# AnalogConversion_v1.net
KiCad netlist of a schematic drawn in EAGLE
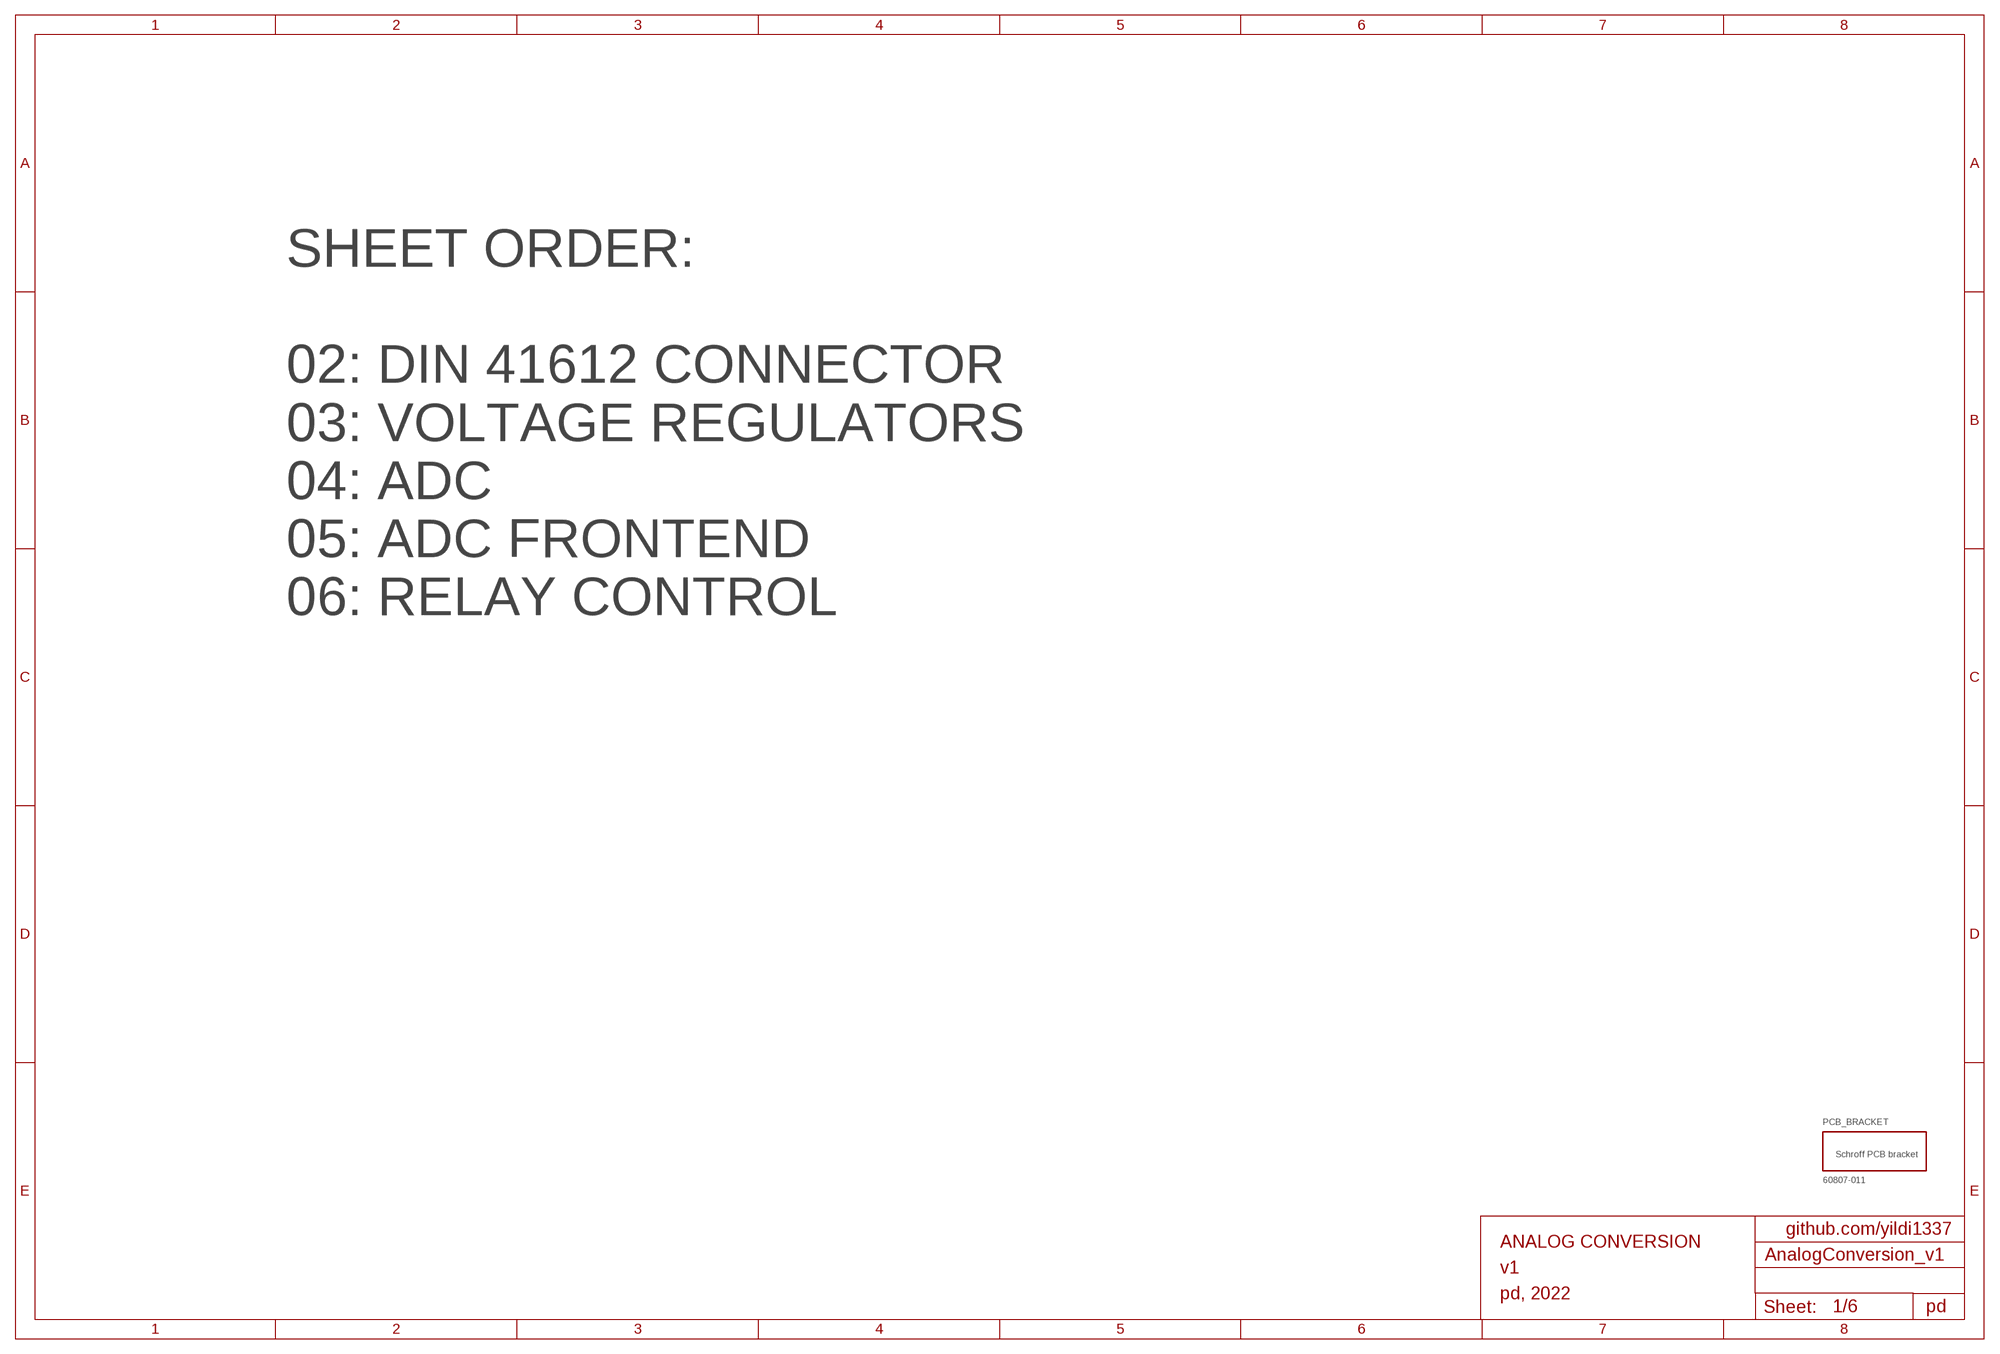
[diagram p0: schematic, sheet 1]
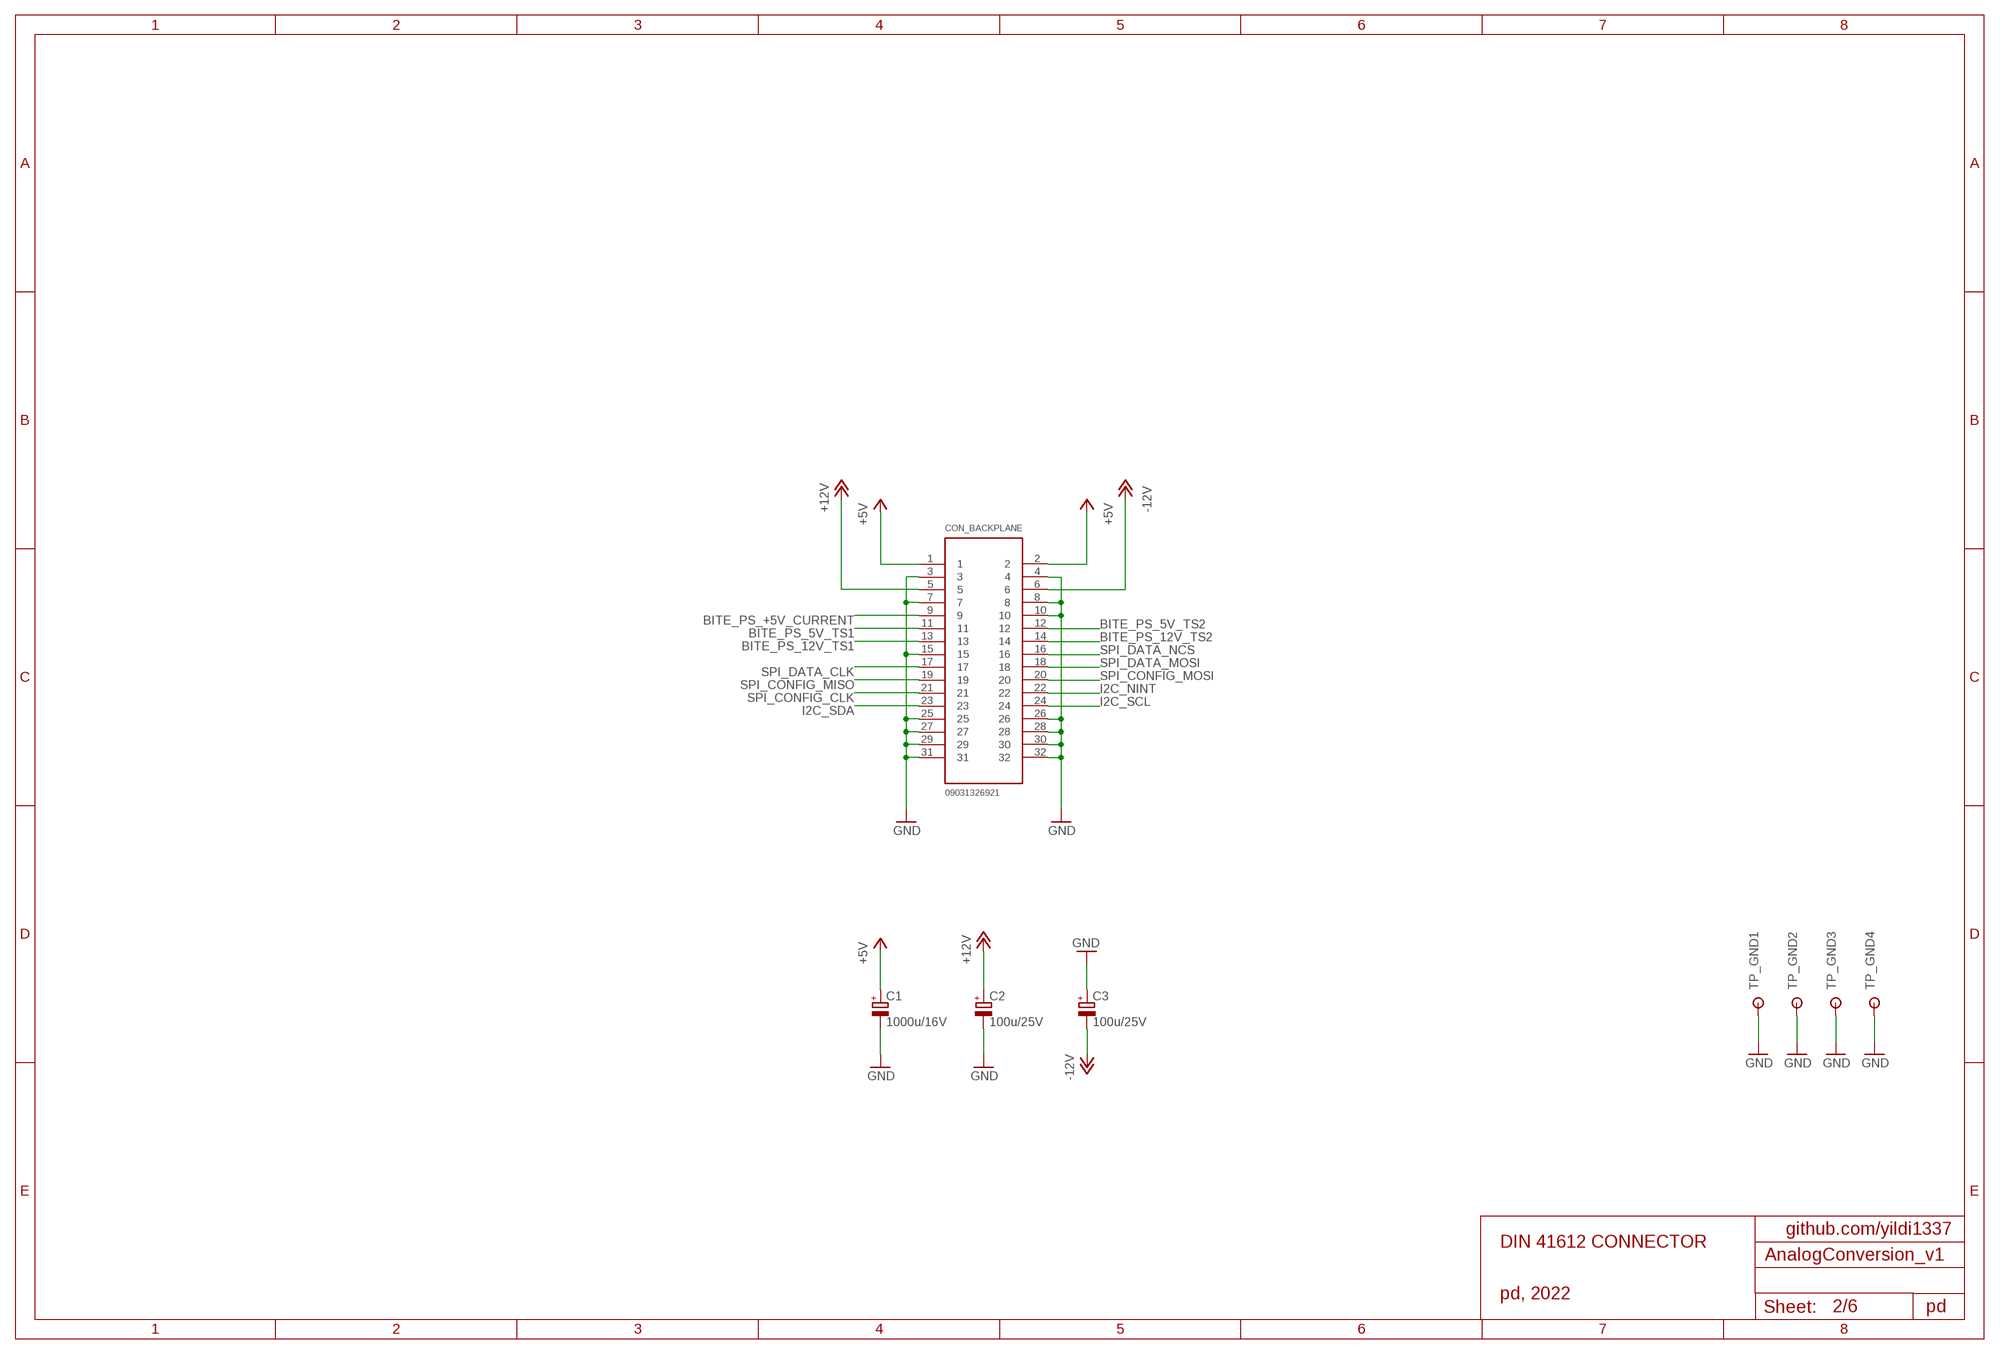
[diagram p1: schematic, sheet 2]
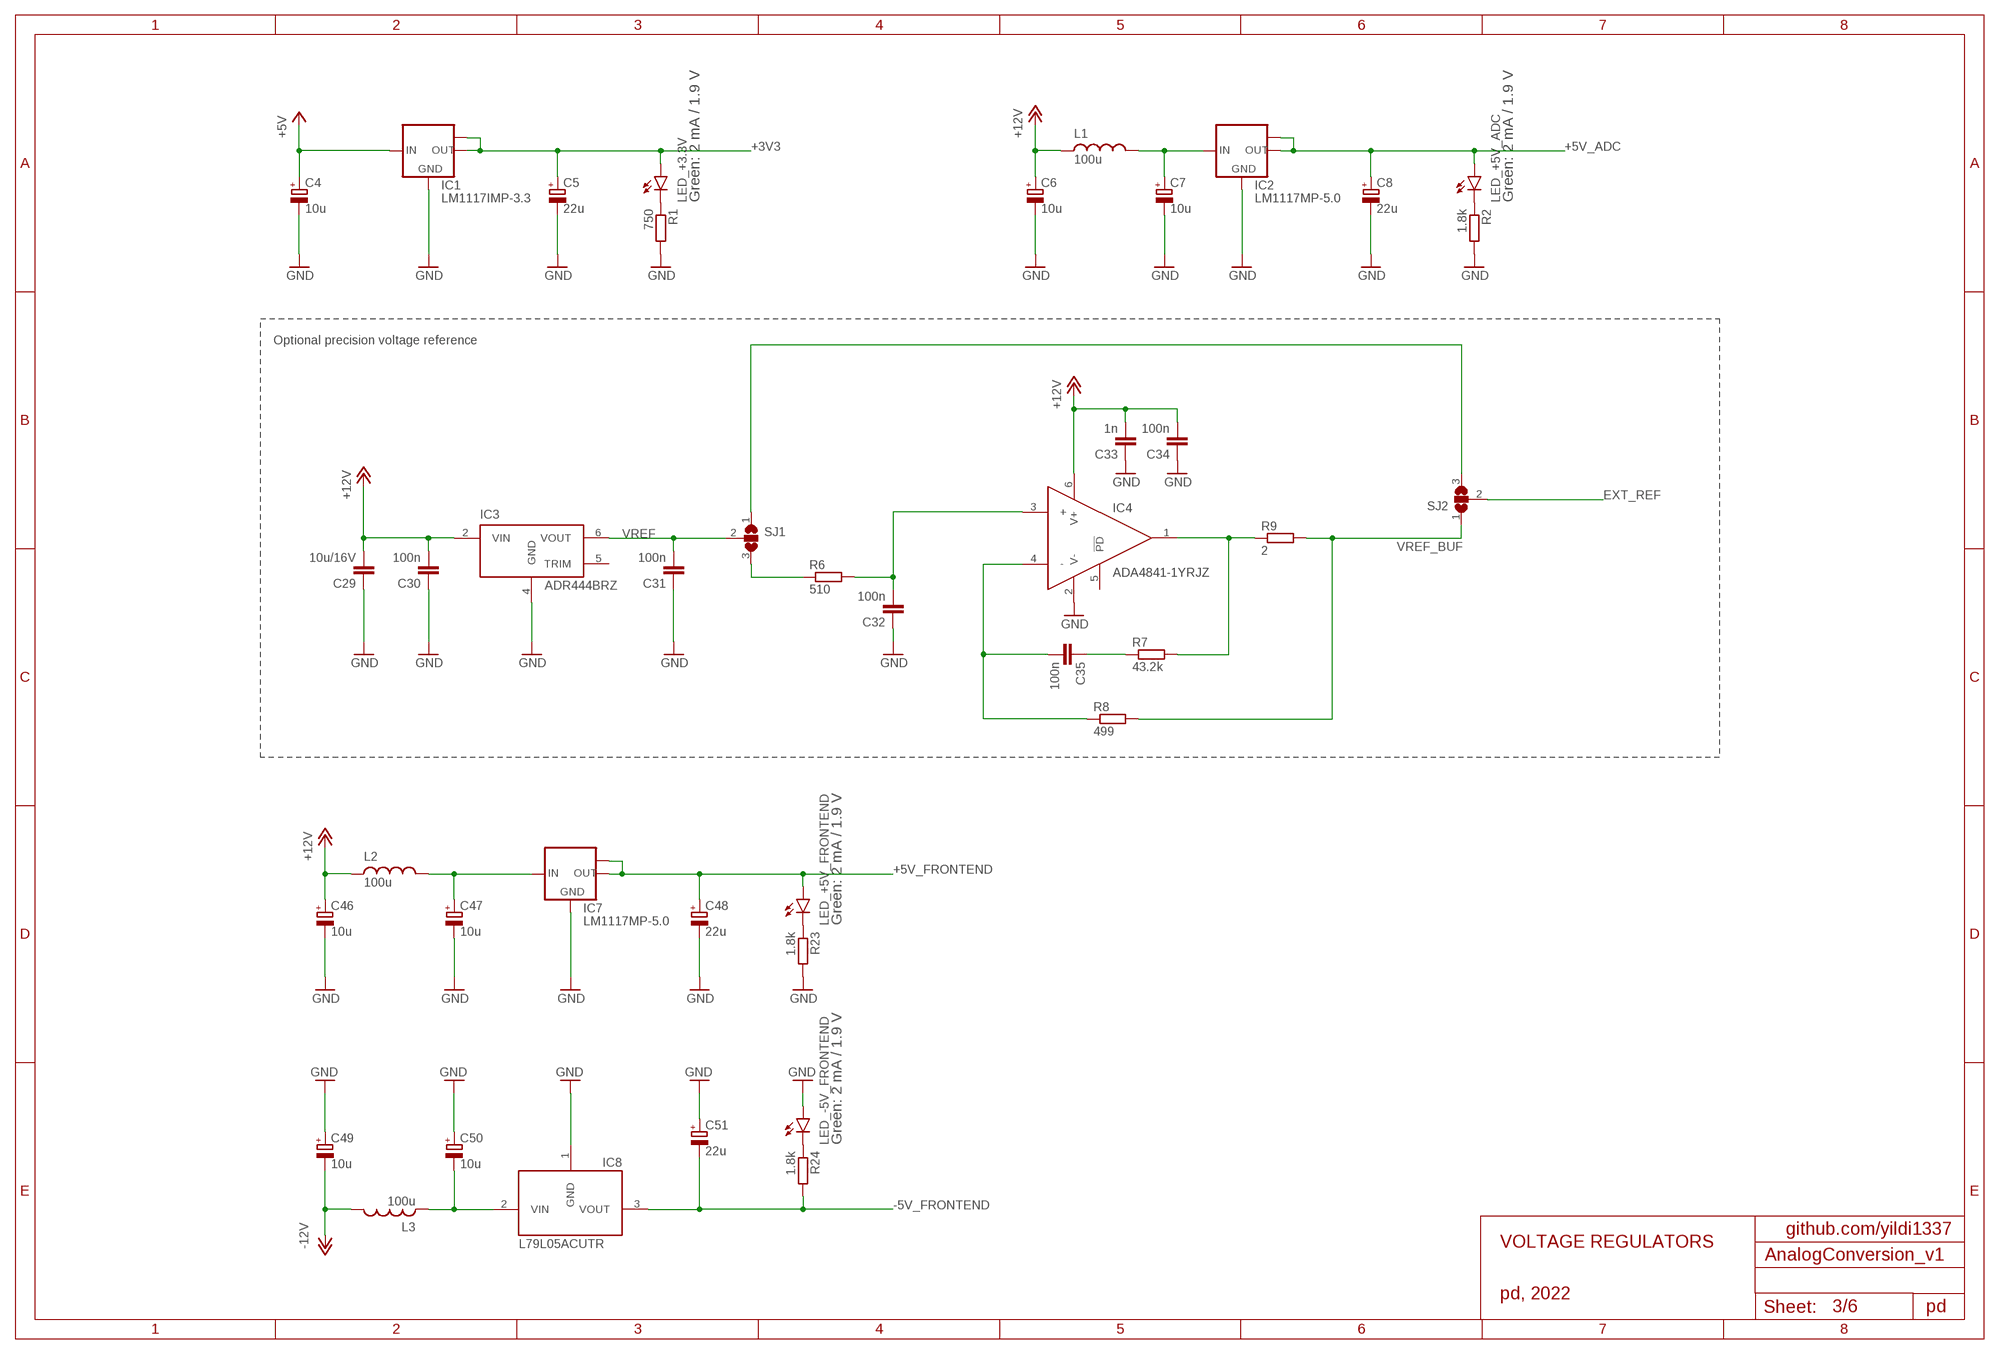
[diagram p2: schematic, sheet 3]
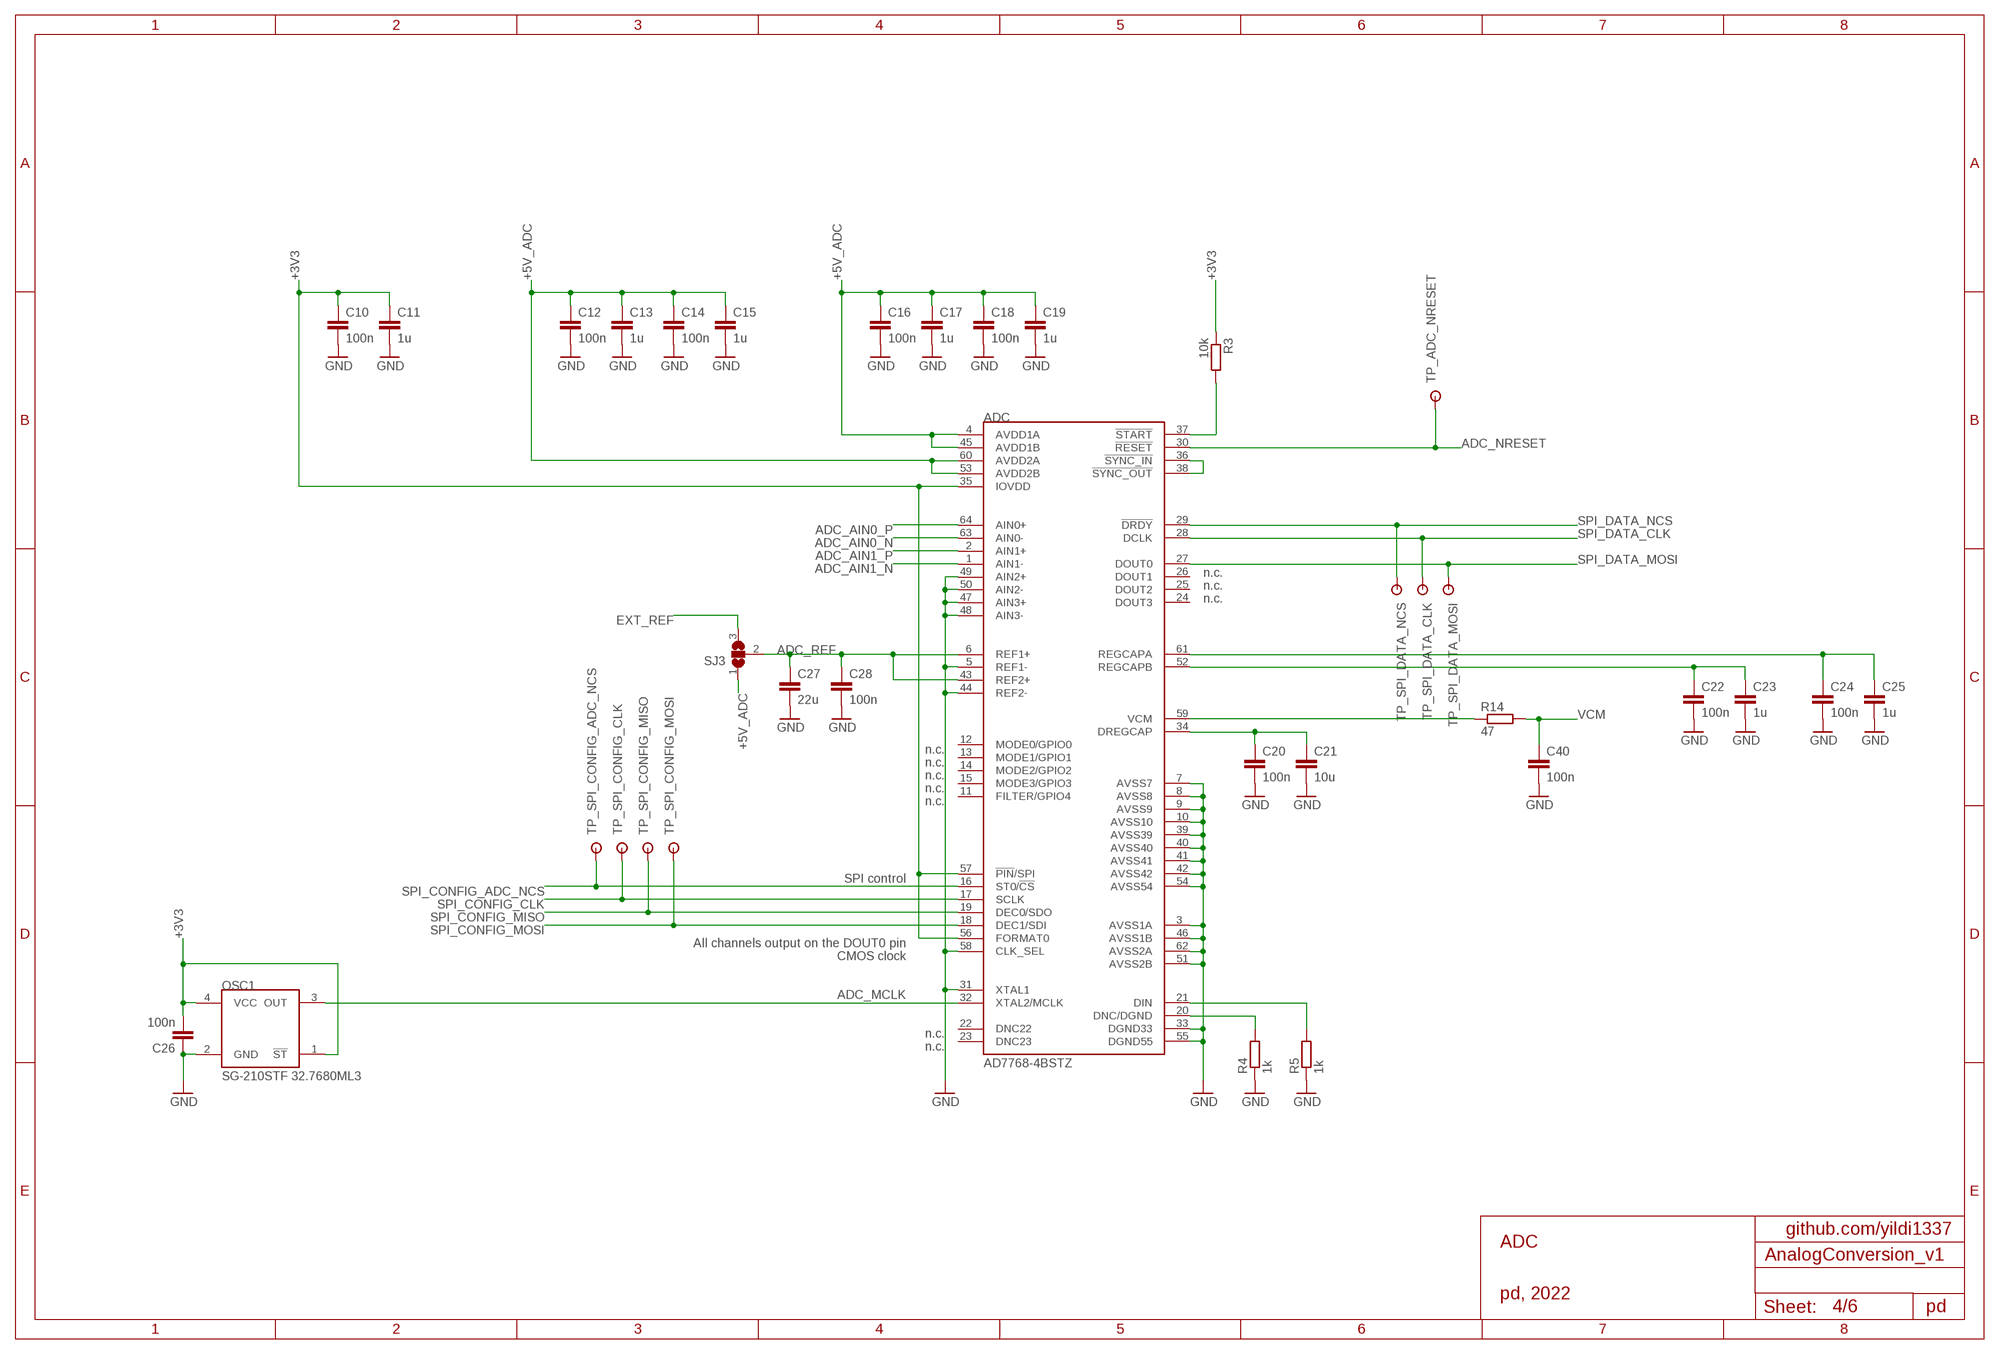
[diagram p3: schematic, sheet 4]
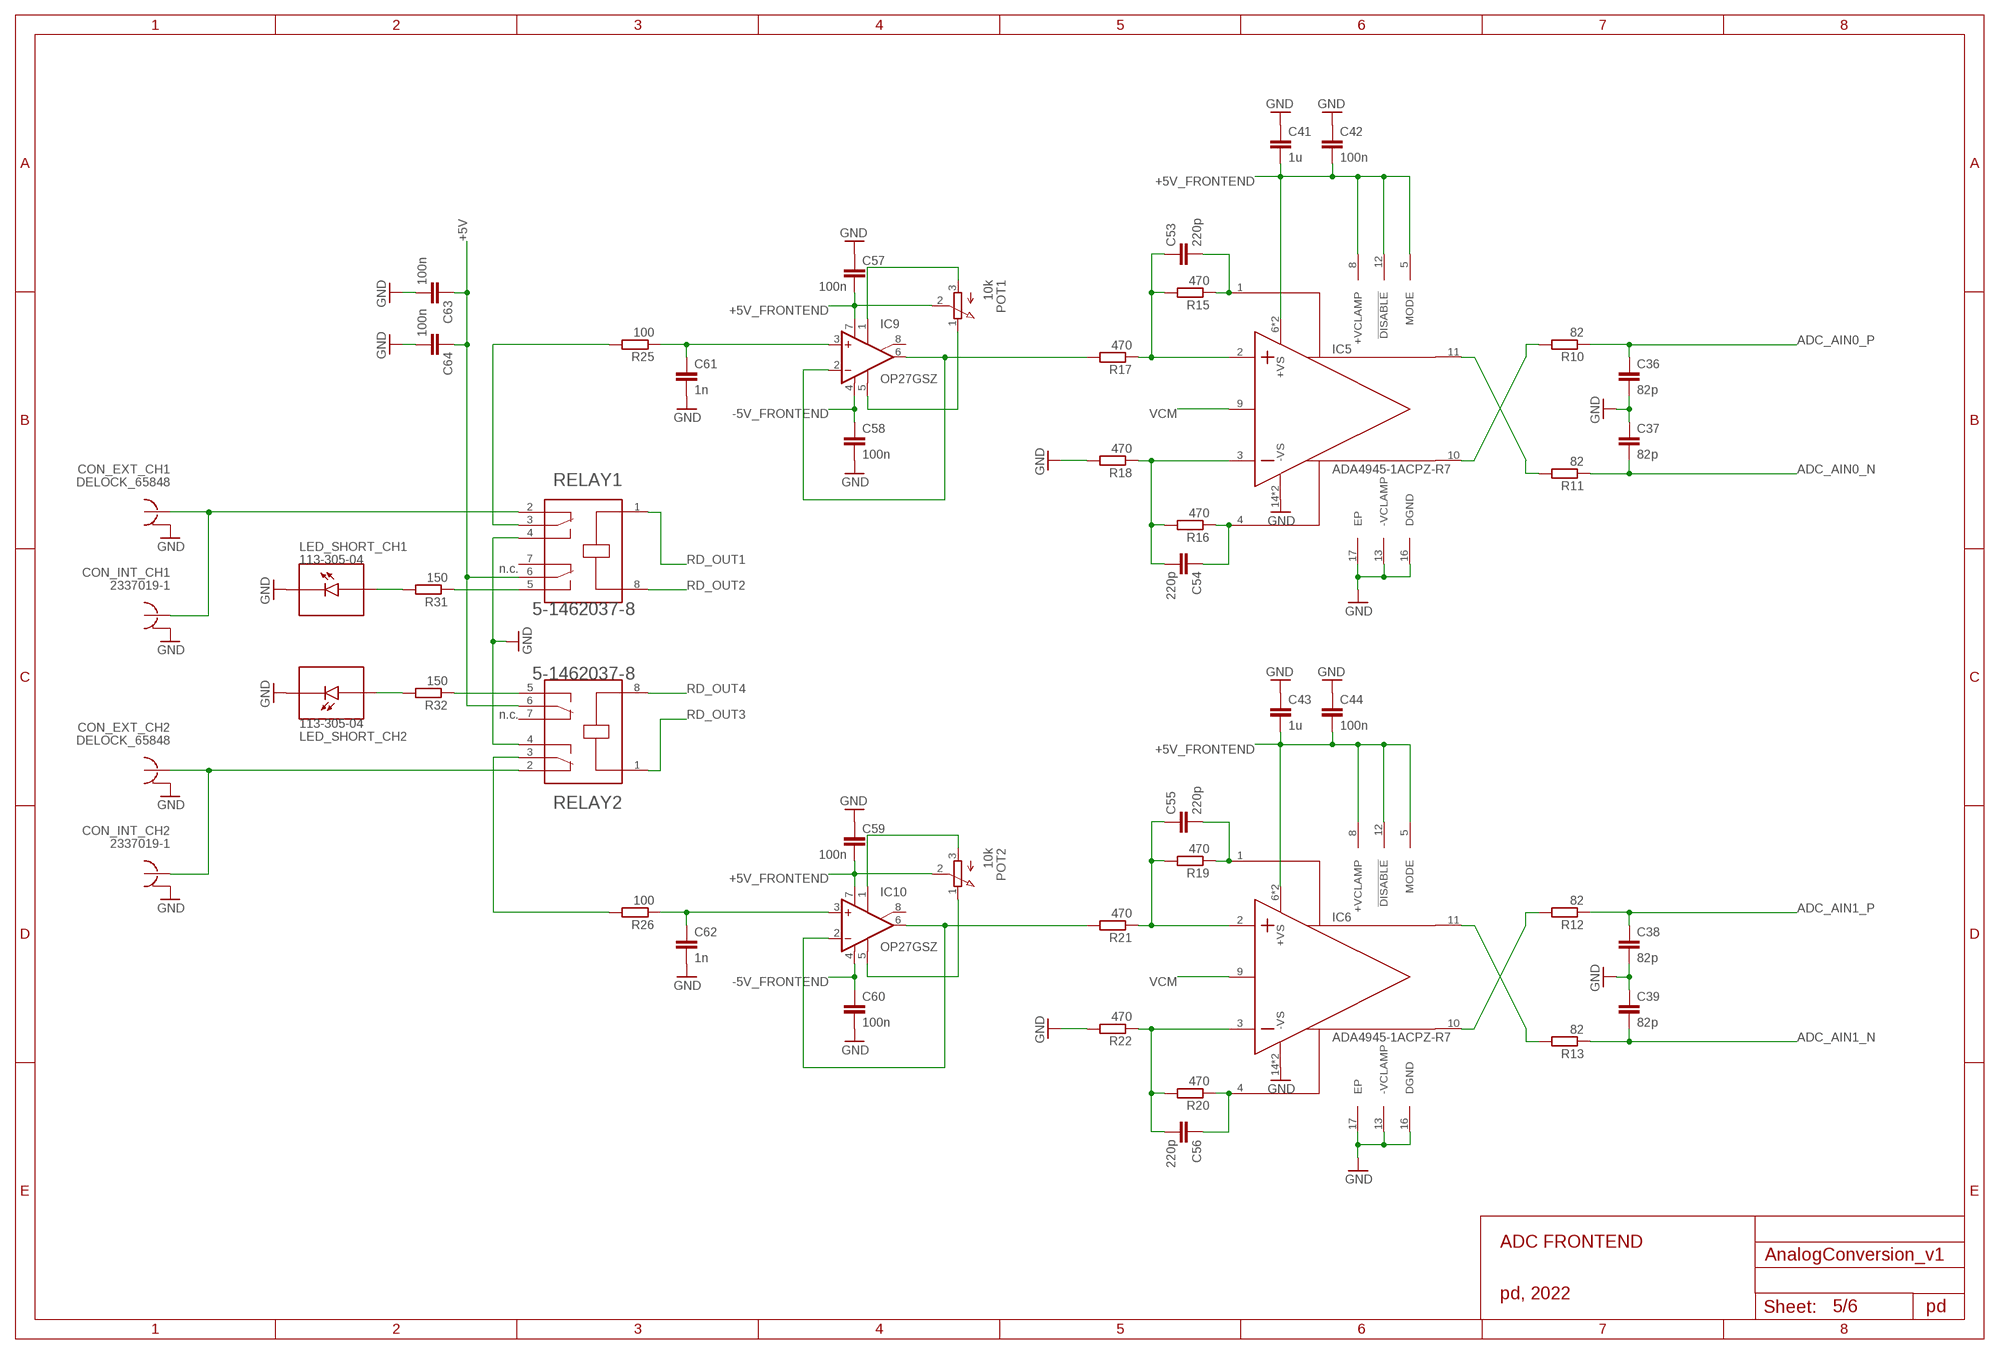
[diagram p4: schematic, sheet 5]
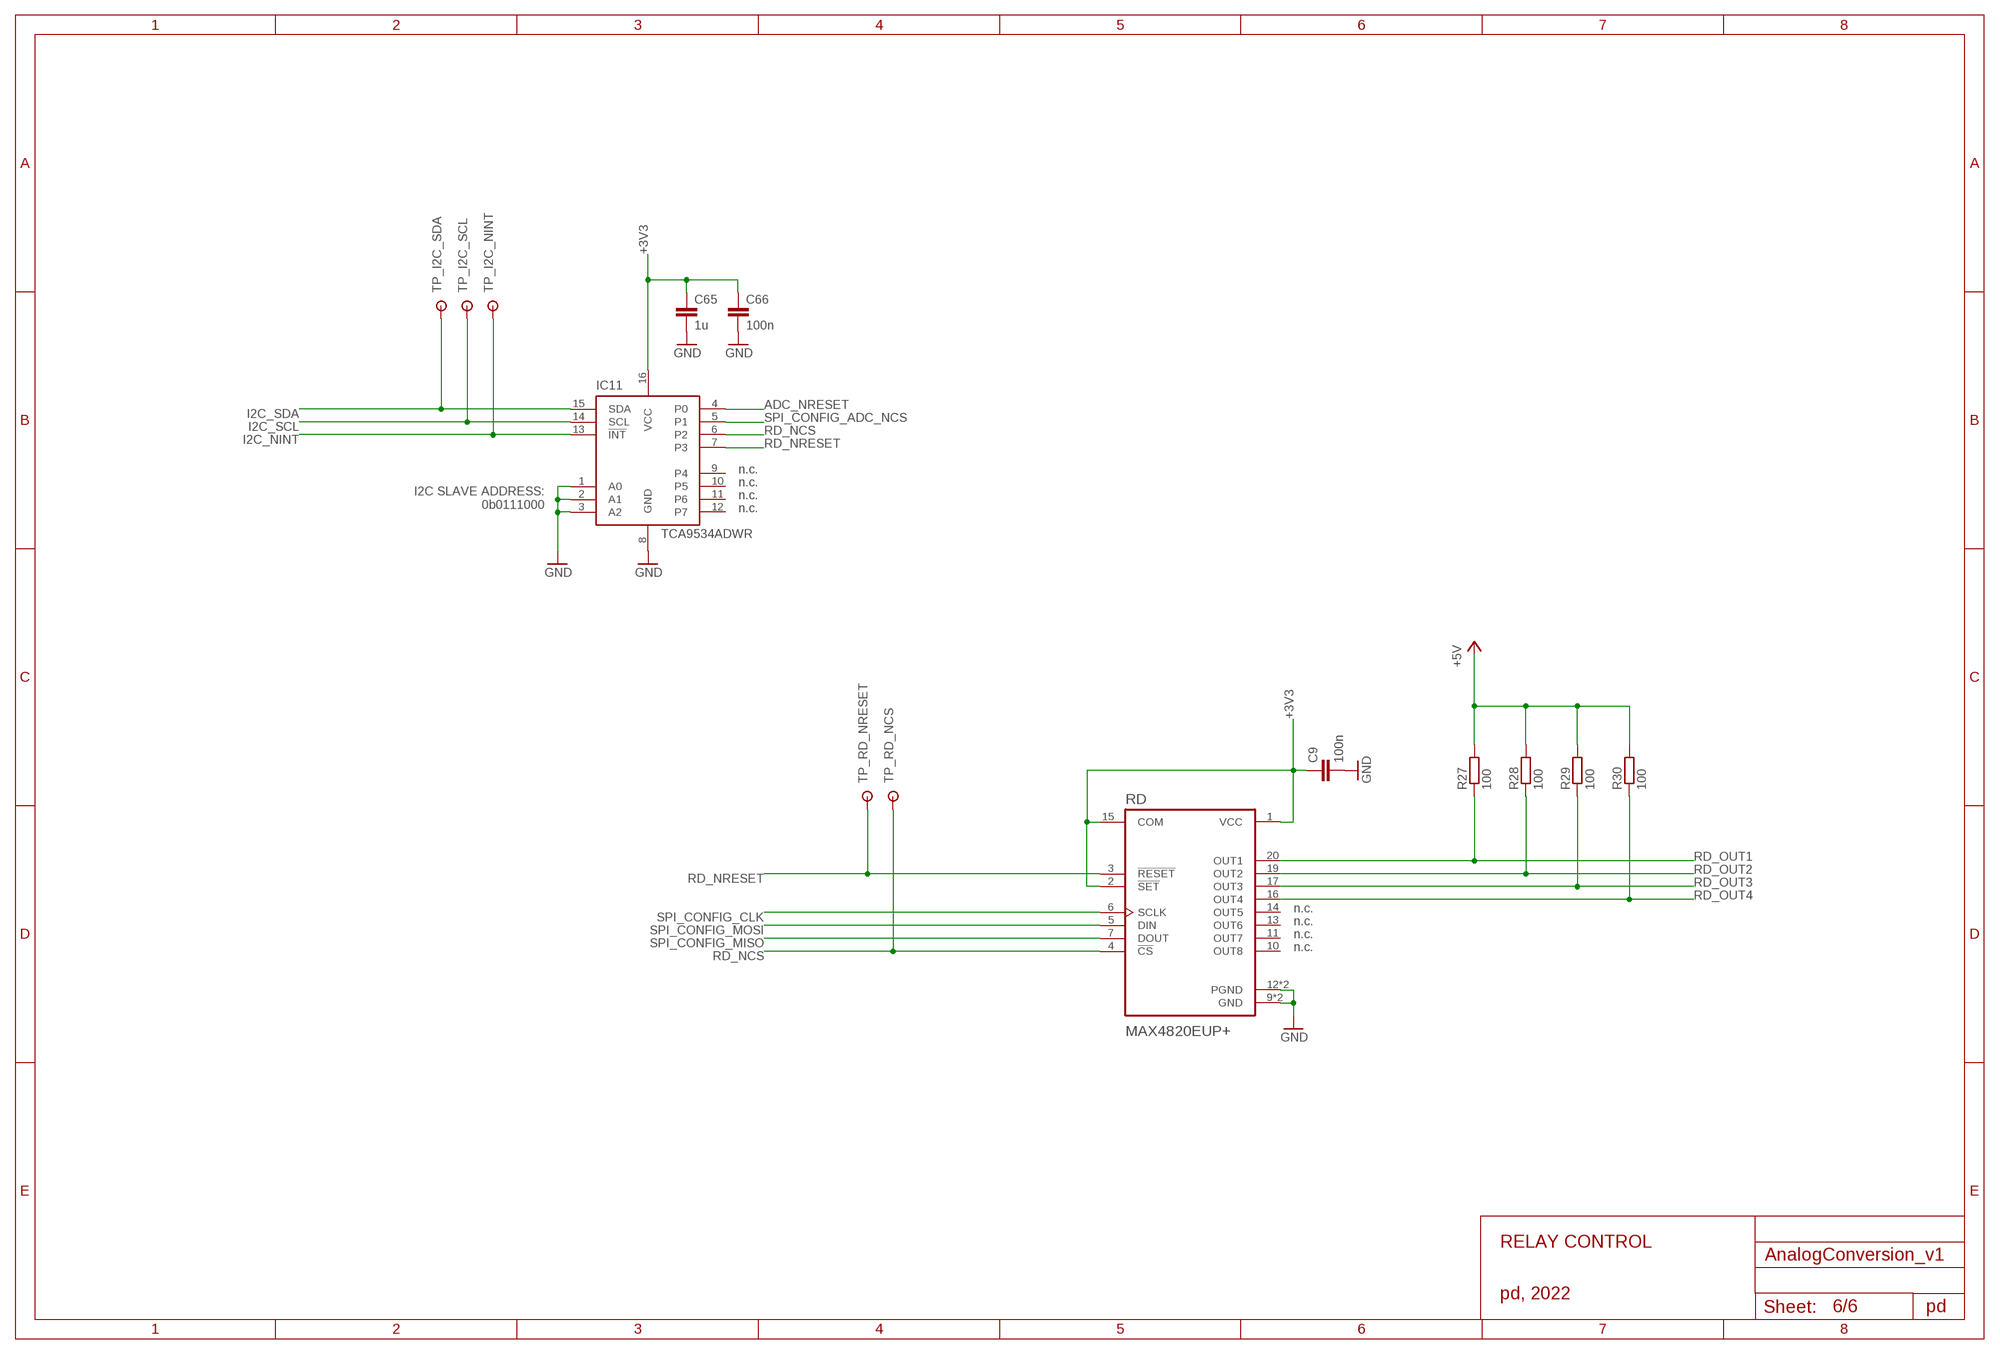
[diagram p5: schematic, sheet 6]

(export (version "E")
  (design (tool "Eeschema 10.0.6"))
  (components
    (comp (ref "C4")
      (value "10u")
      (footprint "eagle-import:CT3216")
      (libsource (lib "eagle-import") (part "CPOL-EUCT3216"))
    )
    (comp (ref "C5")
      (value "22u")
      (footprint "eagle-import:CT6032")
      (libsource (lib "eagle-import") (part "CPOL-EUCT6032"))
    )
    (comp (ref "C6")
      (value "10u")
      (footprint "eagle-import:CT3216")
      (libsource (lib "eagle-import") (part "CPOL-EUCT3216"))
    )
    (comp (ref "C7")
      (value "10u")
      (footprint "eagle-import:CT3216")
      (libsource (lib "eagle-import") (part "CPOL-EUCT3216"))
    )
    (comp (ref "C8")
      (value "22u")
      (footprint "eagle-import:CT6032")
      (libsource (lib "eagle-import") (part "CPOL-EUCT6032"))
    )
    (comp (ref "C29")
      (value "10u/16V")
      (footprint "eagle-import:C0805")
      (libsource (lib "eagle-import") (part "C-EUC0805"))
    )
    (comp (ref "C30")
      (value "100n")
      (footprint "eagle-import:C0603")
      (libsource (lib "eagle-import") (part "C-EUC0603"))
    )
    (comp (ref "C31")
      (value "100n")
      (footprint "eagle-import:C0603")
      (libsource (lib "eagle-import") (part "C-EUC0603"))
    )
    (comp (ref "C32")
      (value "100n")
      (footprint "eagle-import:C0603")
      (libsource (lib "eagle-import") (part "C-EUC0603"))
    )
    (comp (ref "C33")
      (value "1n")
      (footprint "eagle-import:C0603")
      (libsource (lib "eagle-import") (part "C-EUC0603"))
    )
    (comp (ref "C34")
      (value "100n")
      (footprint "eagle-import:C0603")
      (libsource (lib "eagle-import") (part "C-EUC0603"))
    )
    (comp (ref "C35")
      (value "100n")
      (footprint "eagle-import:C0603")
      (libsource (lib "eagle-import") (part "C-EUC0603"))
    )
    (comp (ref "C46")
      (value "10u")
      (footprint "eagle-import:CT3216")
      (libsource (lib "eagle-import") (part "CPOL-EUCT3216"))
    )
    (comp (ref "C47")
      (value "10u")
      (footprint "eagle-import:CT3216")
      (libsource (lib "eagle-import") (part "CPOL-EUCT3216"))
    )
    (comp (ref "C48")
      (value "22u")
      (footprint "eagle-import:CT6032")
      (libsource (lib "eagle-import") (part "CPOL-EUCT6032"))
    )
    (comp (ref "C49")
      (value "10u")
      (footprint "eagle-import:CT3216")
      (libsource (lib "eagle-import") (part "CPOL-EUCT3216"))
    )
    (comp (ref "C50")
      (value "10u")
      (footprint "eagle-import:CT3216")
      (libsource (lib "eagle-import") (part "CPOL-EUCT3216"))
    )
    (comp (ref "C51")
      (value "22u")
      (footprint "eagle-import:CT6032")
      (libsource (lib "eagle-import") (part "CPOL-EUCT6032"))
    )
    (comp (ref "IC1")
      (value "LM1117IMP-3.3")
      (footprint "eagle-import:SOT223")
      (libsource (lib "eagle-import") (part "LM1117IMPX-3.3"))
    )
    (comp (ref "IC2")
      (value "LM1117MP-5.0")
      (footprint "eagle-import:SOT223")
      (libsource (lib "eagle-import") (part "LM1117MPX-5.0"))
    )
    (comp (ref "IC3")
      (value "ADR444BRZ")
      (footprint "eagle-import:ADR444BRZ")
      (libsource (lib "eagle-import") (part "ADR444BRZ"))
    )
    (comp (ref "IC4")
      (value "ADA4841-1YRJZ")
      (footprint "eagle-import:ADA4841-1YRJZ")
      (libsource (lib "eagle-import") (part "ADA4841-1YRJZ"))
    )
    (comp (ref "IC7")
      (value "LM1117MP-5.0")
      (footprint "eagle-import:SOT223")
      (libsource (lib "eagle-import") (part "LM1117MPX-5.0"))
    )
    (comp (ref "IC8")
      (value "L79L05ACUTR")
      (footprint "eagle-import:L79L05ACUTR")
      (libsource (lib "eagle-import") (part "L79L05ACUTR"))
    )
    (comp (ref "L1")
      (value "100u")
      (footprint "eagle-import:VLS6045AF-101M")
      (libsource (lib "eagle-import") (part "VLS6045AF-101M"))
    )
    (comp (ref "L2")
      (value "100u")
      (footprint "eagle-import:VLS6045AF-101M")
      (libsource (lib "eagle-import") (part "VLS6045AF-101M"))
    )
    (comp (ref "L3")
      (value "100u")
      (footprint "eagle-import:VLS6045AF-101M")
      (libsource (lib "eagle-import") (part "VLS6045AF-101M"))
    )
    (comp (ref "LED_+3.3V")
      (value "LEDCHIP-LED0603")
      (footprint "eagle-import:CHIP-LED0603")
      (libsource (lib "eagle-import") (part "LEDCHIP-LED0603"))
    )
    (comp (ref "LED_+5V_ADC")
      (value "LEDCHIP-LED0603")
      (footprint "eagle-import:CHIP-LED0603")
      (libsource (lib "eagle-import") (part "LEDCHIP-LED0603"))
    )
    (comp (ref "LED_+5V_FRONTEND")
      (value "LEDCHIP-LED0603")
      (footprint "eagle-import:CHIP-LED0603")
      (libsource (lib "eagle-import") (part "LEDCHIP-LED0603"))
    )
    (comp (ref "LED_-5V_FRONTEND")
      (value "LEDCHIP-LED0603")
      (footprint "eagle-import:CHIP-LED0603")
      (libsource (lib "eagle-import") (part "LEDCHIP-LED0603"))
    )
    (comp (ref "R1")
      (value "750")
      (footprint "eagle-import:R0603")
      (libsource (lib "eagle-import") (part "R-EU_R0603"))
    )
    (comp (ref "R2")
      (value "1.8k")
      (footprint "eagle-import:R0603")
      (libsource (lib "eagle-import") (part "R-EU_R0603"))
    )
    (comp (ref "R6")
      (value "510")
      (footprint "eagle-import:R0603")
      (libsource (lib "eagle-import") (part "R-EU_R0603"))
    )
    (comp (ref "R7")
      (value "43.2k")
      (footprint "eagle-import:R0603")
      (libsource (lib "eagle-import") (part "R-EU_R0603"))
    )
    (comp (ref "R8")
      (value "499")
      (footprint "eagle-import:R0603")
      (libsource (lib "eagle-import") (part "R-EU_R0603"))
    )
    (comp (ref "R9")
      (value "2")
      (footprint "eagle-import:R0603")
      (libsource (lib "eagle-import") (part "R-EU_R0603"))
    )
    (comp (ref "R23")
      (value "1.8k")
      (footprint "eagle-import:R0603")
      (libsource (lib "eagle-import") (part "R-EU_R0603"))
    )
    (comp (ref "R24")
      (value "1.8k")
      (footprint "eagle-import:R0603")
      (libsource (lib "eagle-import") (part "R-EU_R0603"))
    )
    (comp (ref "SJ1")
      (value "SJ2W")
      (footprint "eagle-import:SJ_2")
      (libsource (lib "eagle-import") (part "SJ2W"))
    )
    (comp (ref "SJ2")
      (value "SJ2W")
      (footprint "eagle-import:SJ_2")
      (libsource (lib "eagle-import") (part "SJ2W"))
    )
    (comp (ref "C1")
      (value "1000u/16V")
      (footprint "eagle-import:153CLV-1010")
      (libsource (lib "eagle-import") (part "rcl_18640681_CPOL-EU153CLV-1010"))
    )
    (comp (ref "C2")
      (value "100u/25V")
      (footprint "eagle-import:153CLV-0810")
      (libsource (lib "eagle-import") (part "rcl_18640681_CPOL-EU153CLV-0810"))
    )
    (comp (ref "C3")
      (value "100u/25V")
      (footprint "eagle-import:153CLV-0810")
      (libsource (lib "eagle-import") (part "rcl_18640681_CPOL-EU153CLV-0810"))
    )
    (comp (ref "CON_BACKPLANE")
      (value "09031326921")
      (footprint "eagle-import:09031326921")
      (libsource (lib "eagle-import") (part "09031326921"))
    )
    (comp (ref "TP_GND1")
      (value "RSPRO-1MM-TERMINAL-POST-2622034")
      (footprint "eagle-import:RSPRO-1MM-TERMINAL-POST-2622034")
      (libsource (lib "eagle-import") (part "RSPRO-1MM-TERMINAL-POST-2622034"))
    )
    (comp (ref "TP_GND2")
      (value "RSPRO-1MM-TERMINAL-POST-2622034")
      (footprint "eagle-import:RSPRO-1MM-TERMINAL-POST-2622034")
      (libsource (lib "eagle-import") (part "RSPRO-1MM-TERMINAL-POST-2622034"))
    )
    (comp (ref "TP_GND3")
      (value "RSPRO-1MM-TERMINAL-POST-2622034")
      (footprint "eagle-import:RSPRO-1MM-TERMINAL-POST-2622034")
      (libsource (lib "eagle-import") (part "RSPRO-1MM-TERMINAL-POST-2622034"))
    )
    (comp (ref "TP_GND4")
      (value "RSPRO-1MM-TERMINAL-POST-2622034")
      (footprint "eagle-import:RSPRO-1MM-TERMINAL-POST-2622034")
      (libsource (lib "eagle-import") (part "RSPRO-1MM-TERMINAL-POST-2622034"))
    )
    (comp (ref "C9")
      (value "100n")
      (footprint "eagle-import:C0603")
      (libsource (lib "eagle-import") (part "C-EUC0603"))
    )
    (comp (ref "C65")
      (value "1u")
      (footprint "eagle-import:C0603")
      (libsource (lib "eagle-import") (part "C-EUC0603"))
    )
    (comp (ref "C66")
      (value "100n")
      (footprint "eagle-import:C0603")
      (libsource (lib "eagle-import") (part "C-EUC0603"))
    )
    (comp (ref "IC11")
      (value "TCA9534ADWR")
      (footprint "eagle-import:TCA9534ADWR")
      (libsource (lib "eagle-import") (part "TCA9534ADWR"))
    )
    (comp (ref "R27")
      (value "100")
      (footprint "eagle-import:R0603")
      (libsource (lib "eagle-import") (part "R-EU_R0603"))
    )
    (comp (ref "R28")
      (value "100")
      (footprint "eagle-import:R0603")
      (libsource (lib "eagle-import") (part "R-EU_R0603"))
    )
    (comp (ref "R29")
      (value "100")
      (footprint "eagle-import:R0603")
      (libsource (lib "eagle-import") (part "R-EU_R0603"))
    )
    (comp (ref "R30")
      (value "100")
      (footprint "eagle-import:R0603")
      (libsource (lib "eagle-import") (part "R-EU_R0603"))
    )
    (comp (ref "RD")
      (value "MAX4820EUP+")
      (footprint "eagle-import:MAX4820EUP+")
      (libsource (lib "eagle-import") (part "MAX4820EUP+"))
    )
    (comp (ref "TP_I2C_NINT")
      (value "RSPRO-1MM-TERMINAL-POST-2622034")
      (footprint "eagle-import:RSPRO-1MM-TERMINAL-POST-2622034")
      (libsource (lib "eagle-import") (part "RSPRO-1MM-TERMINAL-POST-2622034"))
    )
    (comp (ref "TP_I2C_SCL")
      (value "RSPRO-1MM-TERMINAL-POST-2622034")
      (footprint "eagle-import:RSPRO-1MM-TERMINAL-POST-2622034")
      (libsource (lib "eagle-import") (part "RSPRO-1MM-TERMINAL-POST-2622034"))
    )
    (comp (ref "TP_I2C_SDA")
      (value "RSPRO-1MM-TERMINAL-POST-2622034")
      (footprint "eagle-import:RSPRO-1MM-TERMINAL-POST-2622034")
      (libsource (lib "eagle-import") (part "RSPRO-1MM-TERMINAL-POST-2622034"))
    )
    (comp (ref "TP_RD_NCS")
      (value "RSPRO-1MM-TERMINAL-POST-2622034")
      (footprint "eagle-import:RSPRO-1MM-TERMINAL-POST-2622034")
      (libsource (lib "eagle-import") (part "RSPRO-1MM-TERMINAL-POST-2622034"))
    )
    (comp (ref "TP_RD_NRESET")
      (value "RSPRO-1MM-TERMINAL-POST-2622034")
      (footprint "eagle-import:RSPRO-1MM-TERMINAL-POST-2622034")
      (libsource (lib "eagle-import") (part "RSPRO-1MM-TERMINAL-POST-2622034"))
    )
    (comp (ref "PCB_BRACKET")
      (value "60807-011")
      (footprint "eagle-import:60807-011")
      (libsource (lib "eagle-import") (part "60807-011"))
    )
    (comp (ref "ADC")
      (value "AD7768-4BSTZ")
      (footprint "eagle-import:AD7768-4BSTZ")
      (libsource (lib "eagle-import") (part "AD7768-4BSTZ"))
    )
    (comp (ref "C10")
      (value "100n")
      (footprint "eagle-import:C0603")
      (libsource (lib "eagle-import") (part "C-EUC0603"))
    )
    (comp (ref "C11")
      (value "1u")
      (footprint "eagle-import:C0603")
      (libsource (lib "eagle-import") (part "C-EUC0603"))
    )
    (comp (ref "C12")
      (value "100n")
      (footprint "eagle-import:C0603")
      (libsource (lib "eagle-import") (part "C-EUC0603"))
    )
    (comp (ref "C13")
      (value "1u")
      (footprint "eagle-import:C0603")
      (libsource (lib "eagle-import") (part "C-EUC0603"))
    )
    (comp (ref "C14")
      (value "100n")
      (footprint "eagle-import:C0603")
      (libsource (lib "eagle-import") (part "C-EUC0603"))
    )
    (comp (ref "C15")
      (value "1u")
      (footprint "eagle-import:C0603")
      (libsource (lib "eagle-import") (part "C-EUC0603"))
    )
    (comp (ref "C16")
      (value "100n")
      (footprint "eagle-import:C0603")
      (libsource (lib "eagle-import") (part "C-EUC0603"))
    )
    (comp (ref "C17")
      (value "1u")
      (footprint "eagle-import:C0603")
      (libsource (lib "eagle-import") (part "C-EUC0603"))
    )
    (comp (ref "C18")
      (value "100n")
      (footprint "eagle-import:C0603")
      (libsource (lib "eagle-import") (part "C-EUC0603"))
    )
    (comp (ref "C19")
      (value "1u")
      (footprint "eagle-import:C0603")
      (libsource (lib "eagle-import") (part "C-EUC0603"))
    )
    (comp (ref "C20")
      (value "100n")
      (footprint "eagle-import:C0603")
      (libsource (lib "eagle-import") (part "C-EUC0603"))
    )
    (comp (ref "C21")
      (value "10u")
      (footprint "eagle-import:C0603")
      (libsource (lib "eagle-import") (part "C-EUC0603"))
    )
    (comp (ref "C22")
      (value "100n")
      (footprint "eagle-import:C0603")
      (libsource (lib "eagle-import") (part "C-EUC0603"))
    )
    (comp (ref "C23")
      (value "1u")
      (footprint "eagle-import:C0603")
      (libsource (lib "eagle-import") (part "C-EUC0603"))
    )
    (comp (ref "C24")
      (value "100n")
      (footprint "eagle-import:C0603")
      (libsource (lib "eagle-import") (part "C-EUC0603"))
    )
    (comp (ref "C25")
      (value "1u")
      (footprint "eagle-import:C0603")
      (libsource (lib "eagle-import") (part "C-EUC0603"))
    )
    (comp (ref "C26")
      (value "100n")
      (footprint "eagle-import:C0603")
      (libsource (lib "eagle-import") (part "C-EUC0603"))
    )
    (comp (ref "C27")
      (value "22u")
      (footprint "eagle-import:C1206")
      (libsource (lib "eagle-import") (part "C-EUC1206"))
    )
    (comp (ref "C28")
      (value "100n")
      (footprint "eagle-import:C0603")
      (libsource (lib "eagle-import") (part "C-EUC0603"))
    )
    (comp (ref "C40")
      (value "100n")
      (footprint "eagle-import:C0603")
      (libsource (lib "eagle-import") (part "C-EUC0603"))
    )
    (comp (ref "OSC1")
      (value "SG-210STF 32.7680ML3")
      (footprint "eagle-import:SG-210STF-32.7680ML3")
      (libsource (lib "eagle-import") (part "SG-210STF-32.7680ML3"))
    )
    (comp (ref "R3")
      (value "10k")
      (footprint "eagle-import:R0603")
      (libsource (lib "eagle-import") (part "R-EU_R0603"))
    )
    (comp (ref "R4")
      (value "1k")
      (footprint "eagle-import:R0603")
      (libsource (lib "eagle-import") (part "R-EU_R0603"))
    )
    (comp (ref "R5")
      (value "1k")
      (footprint "eagle-import:R0603")
      (libsource (lib "eagle-import") (part "R-EU_R0603"))
    )
    (comp (ref "R14")
      (value "47")
      (footprint "eagle-import:R0603")
      (libsource (lib "eagle-import") (part "R-EU_R0603"))
    )
    (comp (ref "SJ3")
      (value "SJ2W")
      (footprint "eagle-import:SJ_2")
      (libsource (lib "eagle-import") (part "SJ2W"))
    )
    (comp (ref "TP_ADC_NRESET")
      (value "RSPRO-1MM-TERMINAL-POST-2622034")
      (footprint "eagle-import:RSPRO-1MM-TERMINAL-POST-2622034")
      (libsource (lib "eagle-import") (part "RSPRO-1MM-TERMINAL-POST-2622034"))
    )
    (comp (ref "TP_SPI_CONFIG_ADC_NCS")
      (value "RSPRO-1MM-TERMINAL-POST-2622034")
      (footprint "eagle-import:RSPRO-1MM-TERMINAL-POST-2622034")
      (libsource (lib "eagle-import") (part "RSPRO-1MM-TERMINAL-POST-2622034"))
    )
    (comp (ref "TP_SPI_CONFIG_CLK")
      (value "RSPRO-1MM-TERMINAL-POST-2622034")
      (footprint "eagle-import:RSPRO-1MM-TERMINAL-POST-2622034")
      (libsource (lib "eagle-import") (part "RSPRO-1MM-TERMINAL-POST-2622034"))
    )
    (comp (ref "TP_SPI_CONFIG_MISO")
      (value "RSPRO-1MM-TERMINAL-POST-2622034")
      (footprint "eagle-import:RSPRO-1MM-TERMINAL-POST-2622034")
      (libsource (lib "eagle-import") (part "RSPRO-1MM-TERMINAL-POST-2622034"))
    )
    (comp (ref "TP_SPI_CONFIG_MOSI")
      (value "RSPRO-1MM-TERMINAL-POST-2622034")
      (footprint "eagle-import:RSPRO-1MM-TERMINAL-POST-2622034")
      (libsource (lib "eagle-import") (part "RSPRO-1MM-TERMINAL-POST-2622034"))
    )
    (comp (ref "TP_SPI_DATA_CLK")
      (value "RSPRO-1MM-TERMINAL-POST-2622034")
      (footprint "eagle-import:RSPRO-1MM-TERMINAL-POST-2622034")
      (libsource (lib "eagle-import") (part "RSPRO-1MM-TERMINAL-POST-2622034"))
    )
    (comp (ref "TP_SPI_DATA_MOSI")
      (value "RSPRO-1MM-TERMINAL-POST-2622034")
      (footprint "eagle-import:RSPRO-1MM-TERMINAL-POST-2622034")
      (libsource (lib "eagle-import") (part "RSPRO-1MM-TERMINAL-POST-2622034"))
    )
    (comp (ref "TP_SPI_DATA_NCS")
      (value "RSPRO-1MM-TERMINAL-POST-2622034")
      (footprint "eagle-import:RSPRO-1MM-TERMINAL-POST-2622034")
      (libsource (lib "eagle-import") (part "RSPRO-1MM-TERMINAL-POST-2622034"))
    )
    (comp (ref "C36")
      (value "82p")
      (footprint "eagle-import:C0603")
      (libsource (lib "eagle-import") (part "C-EUC0603"))
    )
    (comp (ref "C37")
      (value "82p")
      (footprint "eagle-import:C0603")
      (libsource (lib "eagle-import") (part "C-EUC0603"))
    )
    (comp (ref "C38")
      (value "82p")
      (footprint "eagle-import:C0603")
      (libsource (lib "eagle-import") (part "C-EUC0603"))
    )
    (comp (ref "C39")
      (value "82p")
      (footprint "eagle-import:C0603")
      (libsource (lib "eagle-import") (part "C-EUC0603"))
    )
    (comp (ref "C41")
      (value "1u")
      (footprint "eagle-import:C0603")
      (libsource (lib "eagle-import") (part "C-EUC0603"))
    )
    (comp (ref "C42")
      (value "100n")
      (footprint "eagle-import:C0603")
      (libsource (lib "eagle-import") (part "C-EUC0603"))
    )
    (comp (ref "C43")
      (value "1u")
      (footprint "eagle-import:C0603")
      (libsource (lib "eagle-import") (part "C-EUC0603"))
    )
    (comp (ref "C44")
      (value "100n")
      (footprint "eagle-import:C0603")
      (libsource (lib "eagle-import") (part "C-EUC0603"))
    )
    (comp (ref "C53")
      (value "220p")
      (footprint "eagle-import:C0603")
      (libsource (lib "eagle-import") (part "C-EUC0603"))
    )
    (comp (ref "C54")
      (value "220p")
      (footprint "eagle-import:C0603")
      (libsource (lib "eagle-import") (part "C-EUC0603"))
    )
    (comp (ref "C55")
      (value "220p")
      (footprint "eagle-import:C0603")
      (libsource (lib "eagle-import") (part "C-EUC0603"))
    )
    (comp (ref "C56")
      (value "220p")
      (footprint "eagle-import:C0603")
      (libsource (lib "eagle-import") (part "C-EUC0603"))
    )
    (comp (ref "C57")
      (value "100n")
      (footprint "eagle-import:C0603")
      (libsource (lib "eagle-import") (part "C-EUC0603"))
    )
    (comp (ref "C58")
      (value "100n")
      (footprint "eagle-import:C0603")
      (libsource (lib "eagle-import") (part "C-EUC0603"))
    )
    (comp (ref "C59")
      (value "100n")
      (footprint "eagle-import:C0603")
      (libsource (lib "eagle-import") (part "C-EUC0603"))
    )
    (comp (ref "C60")
      (value "100n")
      (footprint "eagle-import:C0603")
      (libsource (lib "eagle-import") (part "C-EUC0603"))
    )
    (comp (ref "C61")
      (value "1n")
      (footprint "eagle-import:C0603")
      (libsource (lib "eagle-import") (part "C-EUC0603"))
    )
    (comp (ref "C62")
      (value "1n")
      (footprint "eagle-import:C0603")
      (libsource (lib "eagle-import") (part "C-EUC0603"))
    )
    (comp (ref "C63")
      (value "100n")
      (footprint "eagle-import:C0603")
      (libsource (lib "eagle-import") (part "C-EUC0603"))
    )
    (comp (ref "C64")
      (value "100n")
      (footprint "eagle-import:C0603")
      (libsource (lib "eagle-import") (part "C-EUC0603"))
    )
    (comp (ref "CON_EXT_CH1")
      (value "DELOCK_65848")
      (footprint "eagle-import:DELOCK_65848")
      (libsource (lib "eagle-import") (part "DELOCK_65848"))
    )
    (comp (ref "CON_EXT_CH2")
      (value "DELOCK_65848")
      (footprint "eagle-import:DELOCK_65848")
      (libsource (lib "eagle-import") (part "DELOCK_65848"))
    )
    (comp (ref "CON_INT_CH1")
      (value "2337019-1")
      (footprint "eagle-import:2337019-1")
      (libsource (lib "eagle-import") (part "2337019-1"))
    )
    (comp (ref "CON_INT_CH2")
      (value "2337019-1")
      (footprint "eagle-import:2337019-1")
      (libsource (lib "eagle-import") (part "2337019-1"))
    )
    (comp (ref "IC5")
      (value "ADA4945-1ACPZ-R7")
      (footprint "eagle-import:ADA4945-1ACPZ-R7")
      (libsource (lib "eagle-import") (part "ADA4945-1ACPZ-R7"))
    )
    (comp (ref "IC6")
      (value "ADA4945-1ACPZ-R7")
      (footprint "eagle-import:ADA4945-1ACPZ-R7")
      (libsource (lib "eagle-import") (part "ADA4945-1ACPZ-R7"))
    )
    (comp (ref "IC9")
      (value "OP27GSZ")
      (footprint "eagle-import:SO08")
      (libsource (lib "eagle-import") (part "OP27D"))
    )
    (comp (ref "IC10")
      (value "OP27GSZ")
      (footprint "eagle-import:SO08")
      (libsource (lib "eagle-import") (part "OP27D"))
    )
    (comp (ref "LED_SHORT_CH1")
      (value "113-305-04")
      (footprint "eagle-import:113-305-04")
      (libsource (lib "eagle-import") (part "113-305-04"))
    )
    (comp (ref "LED_SHORT_CH2")
      (value "113-305-04")
      (footprint "eagle-import:113-305-04")
      (libsource (lib "eagle-import") (part "113-305-04"))
    )
    (comp (ref "POT1")
      (value "10k")
      (footprint "eagle-import:3296W")
      (libsource (lib "eagle-import") (part "3296W"))
    )
    (comp (ref "POT2")
      (value "10k")
      (footprint "eagle-import:3296W")
      (libsource (lib "eagle-import") (part "3296W"))
    )
    (comp (ref "R10")
      (value "82")
      (footprint "eagle-import:R0603")
      (libsource (lib "eagle-import") (part "R-EU_R0603"))
    )
    (comp (ref "R11")
      (value "82")
      (footprint "eagle-import:R0603")
      (libsource (lib "eagle-import") (part "R-EU_R0603"))
    )
    (comp (ref "R12")
      (value "82")
      (footprint "eagle-import:R0603")
      (libsource (lib "eagle-import") (part "R-EU_R0603"))
    )
    (comp (ref "R13")
      (value "82")
      (footprint "eagle-import:R0603")
      (libsource (lib "eagle-import") (part "R-EU_R0603"))
    )
    (comp (ref "R15")
      (value "470")
      (footprint "eagle-import:R0603")
      (libsource (lib "eagle-import") (part "R-EU_R0603"))
    )
    (comp (ref "R16")
      (value "470")
      (footprint "eagle-import:R0603")
      (libsource (lib "eagle-import") (part "R-EU_R0603"))
    )
    (comp (ref "R17")
      (value "470")
      (footprint "eagle-import:R0603")
      (libsource (lib "eagle-import") (part "R-EU_R0603"))
    )
    (comp (ref "R18")
      (value "470")
      (footprint "eagle-import:R0603")
      (libsource (lib "eagle-import") (part "R-EU_R0603"))
    )
    (comp (ref "R19")
      (value "470")
      (footprint "eagle-import:R0603")
      (libsource (lib "eagle-import") (part "R-EU_R0603"))
    )
    (comp (ref "R20")
      (value "470")
      (footprint "eagle-import:R0603")
      (libsource (lib "eagle-import") (part "R-EU_R0603"))
    )
    (comp (ref "R21")
      (value "470")
      (footprint "eagle-import:R0603")
      (libsource (lib "eagle-import") (part "R-EU_R0603"))
    )
    (comp (ref "R22")
      (value "470")
      (footprint "eagle-import:R0603")
      (libsource (lib "eagle-import") (part "R-EU_R0603"))
    )
    (comp (ref "R25")
      (value "100")
      (footprint "eagle-import:R0603")
      (libsource (lib "eagle-import") (part "R-EU_R0603"))
    )
    (comp (ref "R26")
      (value "100")
      (footprint "eagle-import:R0603")
      (libsource (lib "eagle-import") (part "R-EU_R0603"))
    )
    (comp (ref "R31")
      (value "150")
      (footprint "eagle-import:R0603")
      (libsource (lib "eagle-import") (part "R-EU_R0603"))
    )
    (comp (ref "R32")
      (value "150")
      (footprint "eagle-import:R0603")
      (libsource (lib "eagle-import") (part "R-EU_R0603"))
    )
    (comp (ref "RELAY1")
      (value "5-1462037-8")
      (footprint "eagle-import:5-1462037-8")
      (libsource (lib "eagle-import") (part "5-1462037-8"))
    )
    (comp (ref "RELAY2")
      (value "5-1462037-8")
      (footprint "eagle-import:5-1462037-8")
      (libsource (lib "eagle-import") (part "5-1462037-8"))
    )
  )
  (nets
    (net (code "1") (name "+3V3") (class "Default")
      (node (ref "ADC") (pin "35") (pinfunction "IOVDD_35") (pintype "power_in"))
      (node (ref "ADC") (pin "56") (pinfunction "FORMAT0_56") (pintype "input"))
      (node (ref "ADC") (pin "57") (pinfunction "~{PIN}/SPI_57") (pintype "input"))
      (node (ref "C10") (pin "1") (pinfunction "1_1") (pintype "passive"))
      (node (ref "C11") (pin "1") (pinfunction "1_1") (pintype "passive"))
      (node (ref "C26") (pin "2") (pinfunction "2_2") (pintype "passive"))
      (node (ref "C5") (pin "+") (pinfunction "+_+") (pintype "passive"))
      (node (ref "C65") (pin "1") (pinfunction "1_1") (pintype "passive"))
      (node (ref "C66") (pin "1") (pinfunction "1_1") (pintype "passive"))
      (node (ref "C9") (pin "1") (pinfunction "1_1") (pintype "passive"))
      (node (ref "IC1") (pin "2") (pinfunction "OUT_2") (pintype "passive"))
      (node (ref "IC1") (pin "TAB") (pinfunction "OUT1_TAB") (pintype "passive"))
      (node (ref "IC11") (pin "16") (pinfunction "VCC_16") (pintype "power_in"))
      (node (ref "LED_+3.3V") (pin "A") (pinfunction "A_A") (pintype "passive"))
      (node (ref "OSC1") (pin "1") (pinfunction "~{ST}_1") (pintype "bidirectional"))
      (node (ref "OSC1") (pin "4") (pinfunction "VCC_4") (pintype "bidirectional"))
      (node (ref "R3") (pin "1") (pinfunction "1_1") (pintype "passive"))
      (node (ref "RD") (pin "1") (pinfunction "VCC_1") (pintype "power_in"))
      (node (ref "RD") (pin "15") (pinfunction "COM_15") (pintype "input"))
      (node (ref "RD") (pin "2") (pinfunction "~{SET}_2") (pintype "input"))
    )
    (net (code "2") (name "+5V") (class "Default")
      (node (ref "C1") (pin "+") (pinfunction "+_+") (pintype "passive"))
      (node (ref "C4") (pin "+") (pinfunction "+_+") (pintype "passive"))
      (node (ref "C63") (pin "1") (pinfunction "1_1") (pintype "passive"))
      (node (ref "C64") (pin "1") (pinfunction "1_1") (pintype "passive"))
      (node (ref "CON_BACKPLANE") (pin "1") (pinfunction "1_1") (pintype "bidirectional"))
      (node (ref "CON_BACKPLANE") (pin "2") (pinfunction "2_2") (pintype "bidirectional"))
      (node (ref "IC1") (pin "3") (pinfunction "IN_3") (pintype "input"))
      (node (ref "R27") (pin "2") (pinfunction "2_2") (pintype "passive"))
      (node (ref "R28") (pin "2") (pinfunction "2_2") (pintype "passive"))
      (node (ref "R29") (pin "2") (pinfunction "2_2") (pintype "passive"))
      (node (ref "R30") (pin "2") (pinfunction "2_2") (pintype "passive"))
      (node (ref "RELAY1") (pin "6") (pinfunction "6_6") (pintype "passive"))
      (node (ref "RELAY2") (pin "6") (pinfunction "6_6") (pintype "passive"))
    )
    (net (code "3") (name "+5V_ADC") (class "Default")
      (node (ref "ADC") (pin "4") (pinfunction "AVDD1A_4") (pintype "power_in"))
      (node (ref "ADC") (pin "45") (pinfunction "AVDD1B_45") (pintype "passive"))
      (node (ref "ADC") (pin "53") (pinfunction "AVDD2B_53") (pintype "power_in"))
      (node (ref "ADC") (pin "60") (pinfunction "AVDD2A_60") (pintype "power_in"))
      (node (ref "C12") (pin "1") (pinfunction "1_1") (pintype "passive"))
      (node (ref "C13") (pin "1") (pinfunction "1_1") (pintype "passive"))
      (node (ref "C14") (pin "1") (pinfunction "1_1") (pintype "passive"))
      (node (ref "C15") (pin "1") (pinfunction "1_1") (pintype "passive"))
      (node (ref "C16") (pin "1") (pinfunction "1_1") (pintype "passive"))
      (node (ref "C17") (pin "1") (pinfunction "1_1") (pintype "passive"))
      (node (ref "C18") (pin "1") (pinfunction "1_1") (pintype "passive"))
      (node (ref "C19") (pin "1") (pinfunction "1_1") (pintype "passive"))
      (node (ref "C8") (pin "+") (pinfunction "+_+") (pintype "passive"))
      (node (ref "IC2") (pin "2") (pinfunction "OUT_2") (pintype "passive"))
      (node (ref "IC2") (pin "TAB") (pinfunction "OUT1_TAB") (pintype "passive"))
      (node (ref "LED_+5V_ADC") (pin "A") (pinfunction "A_A") (pintype "passive"))
      (node (ref "SJ3") (pin "1") (pinfunction "1_1") (pintype "passive"))
    )
    (net (code "4") (name "+5V_FRONTEND") (class "Default")
      (node (ref "C41") (pin "2") (pinfunction "2_2") (pintype "passive"))
      (node (ref "C42") (pin "2") (pinfunction "2_2") (pintype "passive"))
      (node (ref "C43") (pin "2") (pinfunction "2_2") (pintype "passive"))
      (node (ref "C44") (pin "2") (pinfunction "2_2") (pintype "passive"))
      (node (ref "C48") (pin "+") (pinfunction "+_+") (pintype "passive"))
      (node (ref "C57") (pin "2") (pinfunction "2_2") (pintype "passive"))
      (node (ref "C59") (pin "2") (pinfunction "2_2") (pintype "passive"))
      (node (ref "IC10") (pin "7") (pinfunction "V+_7") (pintype "power_in"))
      (node (ref "IC5") (pin "12") (pinfunction "~{DISABLE}_12") (pintype "input"))
      (node (ref "IC5") (pin "5") (pinfunction "MODE_5") (pintype "input"))
      (node (ref "IC5") (pin "6") (pinfunction "+VS_6") (pintype "power_in"))
      (node (ref "IC5") (pin "7") (pinfunction "+VS_7") (pintype "power_in"))
      (node (ref "IC5") (pin "8") (pinfunction "+VCLAMP_8") (pintype "power_in"))
      (node (ref "IC6") (pin "12") (pinfunction "~{DISABLE}_12") (pintype "input"))
      (node (ref "IC6") (pin "5") (pinfunction "MODE_5") (pintype "input"))
      (node (ref "IC6") (pin "6") (pinfunction "+VS_6") (pintype "power_in"))
      (node (ref "IC6") (pin "7") (pinfunction "+VS_7") (pintype "power_in"))
      (node (ref "IC6") (pin "8") (pinfunction "+VCLAMP_8") (pintype "power_in"))
      (node (ref "IC7") (pin "2") (pinfunction "OUT_2") (pintype "passive"))
      (node (ref "IC7") (pin "TAB") (pinfunction "OUT1_TAB") (pintype "passive"))
      (node (ref "IC9") (pin "7") (pinfunction "V+_7") (pintype "power_in"))
      (node (ref "LED_+5V_FRONTEND") (pin "A") (pinfunction "A_A") (pintype "passive"))
      (node (ref "POT1") (pin "2") (pinfunction "2_2") (pintype "passive"))
      (node (ref "POT2") (pin "2") (pinfunction "2_2") (pintype "passive"))
    )
    (net (code "5") (name "+12V") (class "Default")
      (node (ref "C2") (pin "+") (pinfunction "+_+") (pintype "passive"))
      (node (ref "C29") (pin "2") (pinfunction "2_2") (pintype "passive"))
      (node (ref "C30") (pin "2") (pinfunction "2_2") (pintype "passive"))
      (node (ref "C33") (pin "2") (pinfunction "2_2") (pintype "passive"))
      (node (ref "C34") (pin "2") (pinfunction "2_2") (pintype "passive"))
      (node (ref "C46") (pin "+") (pinfunction "+_+") (pintype "passive"))
      (node (ref "C6") (pin "+") (pinfunction "+_+") (pintype "passive"))
      (node (ref "CON_BACKPLANE") (pin "5") (pinfunction "5_5") (pintype "bidirectional"))
      (node (ref "IC3") (pin "2") (pinfunction "VIN_2") (pintype "bidirectional"))
      (node (ref "IC4") (pin "6") (pinfunction "V+_6") (pintype "bidirectional"))
      (node (ref "L1") (pin "1") (pinfunction "1_1") (pintype "passive"))
      (node (ref "L2") (pin "1") (pinfunction "1_1") (pintype "passive"))
    )
    (net (code "6") (name "-5V_FRONTEND") (class "Default")
      (node (ref "C51") (pin "-") (pinfunction "-_-") (pintype "passive"))
      (node (ref "C58") (pin "1") (pinfunction "1_1") (pintype "passive"))
      (node (ref "C60") (pin "1") (pinfunction "1_1") (pintype "passive"))
      (node (ref "IC10") (pin "4") (pinfunction "V-_4") (pintype "power_in"))
      (node (ref "IC8") (pin "3") (pinfunction "VOUT_3") (pintype "bidirectional"))
      (node (ref "IC9") (pin "4") (pinfunction "V-_4") (pintype "power_in"))
      (node (ref "R24") (pin "2") (pinfunction "2_2") (pintype "passive"))
    )
    (net (code "7") (name "-12V") (class "Default")
      (node (ref "C3") (pin "-") (pinfunction "-_-") (pintype "passive"))
      (node (ref "C49") (pin "-") (pinfunction "-_-") (pintype "passive"))
      (node (ref "CON_BACKPLANE") (pin "6") (pinfunction "6_6") (pintype "bidirectional"))
      (node (ref "L3") (pin "2") (pinfunction "2_2") (pintype "passive"))
    )
    (net (code "8") (name "ADC_AIN0_N") (class "Default")
      (node (ref "ADC") (pin "63") (pinfunction "AIN0-_63") (pintype "input"))
      (node (ref "C37") (pin "2") (pinfunction "2_2") (pintype "passive"))
      (node (ref "R11") (pin "1") (pinfunction "1_1") (pintype "passive"))
    )
    (net (code "9") (name "ADC_AIN0_P") (class "Default")
      (node (ref "ADC") (pin "64") (pinfunction "AIN0+_64") (pintype "input"))
      (node (ref "C36") (pin "1") (pinfunction "1_1") (pintype "passive"))
      (node (ref "R10") (pin "1") (pinfunction "1_1") (pintype "passive"))
    )
    (net (code "10") (name "ADC_AIN1_N") (class "Default")
      (node (ref "ADC") (pin "1") (pinfunction "AIN1-_1") (pintype "input"))
      (node (ref "C39") (pin "2") (pinfunction "2_2") (pintype "passive"))
      (node (ref "R13") (pin "1") (pinfunction "1_1") (pintype "passive"))
    )
    (net (code "11") (name "ADC_AIN1_P") (class "Default")
      (node (ref "ADC") (pin "2") (pinfunction "AIN1+_2") (pintype "input"))
      (node (ref "C38") (pin "1") (pinfunction "1_1") (pintype "passive"))
      (node (ref "R12") (pin "1") (pinfunction "1_1") (pintype "passive"))
    )
    (net (code "12") (name "ADC_MCLK") (class "Default")
      (node (ref "ADC") (pin "32") (pinfunction "XTAL2/MCLK_32") (pintype "input"))
      (node (ref "OSC1") (pin "3") (pinfunction "OUT_3") (pintype "bidirectional"))
    )
    (net (code "13") (name "ADC_NRESET") (class "Default")
      (node (ref "ADC") (pin "30") (pinfunction "~{RESET}_30") (pintype "input"))
      (node (ref "IC11") (pin "4") (pinfunction "P0_4") (pintype "bidirectional"))
      (node (ref "TP_ADC_NRESET") (pin "P$1") (pinfunction "P$1_P$1") (pintype "bidirectional"))
    )
    (net (code "14") (name "ADC_REF") (class "Default")
      (node (ref "ADC") (pin "43") (pinfunction "REF2+_43") (pintype "input"))
      (node (ref "ADC") (pin "6") (pinfunction "REF1+_6") (pintype "input"))
      (node (ref "C27") (pin "1") (pinfunction "1_1") (pintype "passive"))
      (node (ref "C28") (pin "1") (pinfunction "1_1") (pintype "passive"))
      (node (ref "SJ3") (pin "2") (pinfunction "2_2") (pintype "passive"))
    )
    (net (code "15") (name "BITE_PS_+5V_CURRENT") (class "Default")
      (node (ref "CON_BACKPLANE") (pin "9") (pinfunction "9_9") (pintype "bidirectional"))
    )
    (net (code "16") (name "BITE_PS_5V_TS1") (class "Default")
      (node (ref "CON_BACKPLANE") (pin "11") (pinfunction "11_11") (pintype "bidirectional"))
    )
    (net (code "17") (name "BITE_PS_5V_TS2") (class "Default")
      (node (ref "CON_BACKPLANE") (pin "12") (pinfunction "12_12") (pintype "bidirectional"))
    )
    (net (code "18") (name "BITE_PS_12V_TS1") (class "Default")
      (node (ref "CON_BACKPLANE") (pin "13") (pinfunction "13_13") (pintype "bidirectional"))
    )
    (net (code "19") (name "BITE_PS_12V_TS2") (class "Default")
      (node (ref "CON_BACKPLANE") (pin "14") (pinfunction "14_14") (pintype "bidirectional"))
    )
    (net (code "20") (name "EXT_REF") (class "Default")
      (node (ref "SJ2") (pin "2") (pinfunction "2_2") (pintype "passive"))
      (node (ref "SJ3") (pin "3") (pinfunction "3_3") (pintype "passive"))
    )
    (net (code "21") (name "GND") (class "Default")
      (node (ref "ADC") (pin "10") (pinfunction "AVSS10_10") (pintype "power_in"))
      (node (ref "ADC") (pin "3") (pinfunction "AVSS1A_3") (pintype "power_in"))
      (node (ref "ADC") (pin "31") (pinfunction "XTAL1_31") (pintype "input"))
      (node (ref "ADC") (pin "33") (pinfunction "DGND33_33") (pintype "power_in"))
      (node (ref "ADC") (pin "39") (pinfunction "AVSS39_39") (pintype "power_in"))
      (node (ref "ADC") (pin "40") (pinfunction "AVSS40_40") (pintype "power_in"))
      (node (ref "ADC") (pin "41") (pinfunction "AVSS41_41") (pintype "power_in"))
      (node (ref "ADC") (pin "42") (pinfunction "AVSS42_42") (pintype "power_in"))
      (node (ref "ADC") (pin "44") (pinfunction "REF2-_44") (pintype "input"))
      (node (ref "ADC") (pin "46") (pinfunction "AVSS1B_46") (pintype "passive"))
      (node (ref "ADC") (pin "47") (pinfunction "AIN3+_47") (pintype "input"))
      (node (ref "ADC") (pin "48") (pinfunction "AIN3-_48") (pintype "input"))
      (node (ref "ADC") (pin "49") (pinfunction "AIN2+_49") (pintype "input"))
      (node (ref "ADC") (pin "5") (pinfunction "REF1-_5") (pintype "input"))
      (node (ref "ADC") (pin "50") (pinfunction "AIN2-_50") (pintype "input"))
      (node (ref "ADC") (pin "51") (pinfunction "AVSS2B_51") (pintype "power_in"))
      (node (ref "ADC") (pin "54") (pinfunction "AVSS54_54") (pintype "power_in"))
      (node (ref "ADC") (pin "55") (pinfunction "DGND55_55") (pintype "power_in"))
      (node (ref "ADC") (pin "58") (pinfunction "CLK_SEL_58") (pintype "input"))
      (node (ref "ADC") (pin "62") (pinfunction "AVSS2A_62") (pintype "power_in"))
      (node (ref "ADC") (pin "7") (pinfunction "AVSS7_7") (pintype "power_in"))
      (node (ref "ADC") (pin "8") (pinfunction "AVSS8_8") (pintype "power_in"))
      (node (ref "ADC") (pin "9") (pinfunction "AVSS9_9") (pintype "power_in"))
      (node (ref "C1") (pin "-") (pinfunction "-_-") (pintype "passive"))
      (node (ref "C10") (pin "2") (pinfunction "2_2") (pintype "passive"))
      (node (ref "C11") (pin "2") (pinfunction "2_2") (pintype "passive"))
      (node (ref "C12") (pin "2") (pinfunction "2_2") (pintype "passive"))
      (node (ref "C13") (pin "2") (pinfunction "2_2") (pintype "passive"))
      (node (ref "C14") (pin "2") (pinfunction "2_2") (pintype "passive"))
      (node (ref "C15") (pin "2") (pinfunction "2_2") (pintype "passive"))
      (node (ref "C16") (pin "2") (pinfunction "2_2") (pintype "passive"))
      (node (ref "C17") (pin "2") (pinfunction "2_2") (pintype "passive"))
      (node (ref "C18") (pin "2") (pinfunction "2_2") (pintype "passive"))
      (node (ref "C19") (pin "2") (pinfunction "2_2") (pintype "passive"))
      (node (ref "C2") (pin "-") (pinfunction "-_-") (pintype "passive"))
      (node (ref "C20") (pin "2") (pinfunction "2_2") (pintype "passive"))
      (node (ref "C21") (pin "2") (pinfunction "2_2") (pintype "passive"))
      (node (ref "C22") (pin "2") (pinfunction "2_2") (pintype "passive"))
      (node (ref "C23") (pin "2") (pinfunction "2_2") (pintype "passive"))
      (node (ref "C24") (pin "2") (pinfunction "2_2") (pintype "passive"))
      (node (ref "C25") (pin "2") (pinfunction "2_2") (pintype "passive"))
      (node (ref "C26") (pin "1") (pinfunction "1_1") (pintype "passive"))
      (node (ref "C27") (pin "2") (pinfunction "2_2") (pintype "passive"))
      (node (ref "C28") (pin "2") (pinfunction "2_2") (pintype "passive"))
      (node (ref "C29") (pin "1") (pinfunction "1_1") (pintype "passive"))
      (node (ref "C3") (pin "+") (pinfunction "+_+") (pintype "passive"))
      (node (ref "C30") (pin "1") (pinfunction "1_1") (pintype "passive"))
      (node (ref "C31") (pin "1") (pinfunction "1_1") (pintype "passive"))
      (node (ref "C32") (pin "1") (pinfunction "1_1") (pintype "passive"))
      (node (ref "C33") (pin "1") (pinfunction "1_1") (pintype "passive"))
      (node (ref "C34") (pin "1") (pinfunction "1_1") (pintype "passive"))
      (node (ref "C36") (pin "2") (pinfunction "2_2") (pintype "passive"))
      (node (ref "C37") (pin "1") (pinfunction "1_1") (pintype "passive"))
      (node (ref "C38") (pin "2") (pinfunction "2_2") (pintype "passive"))
      (node (ref "C39") (pin "1") (pinfunction "1_1") (pintype "passive"))
      (node (ref "C4") (pin "-") (pinfunction "-_-") (pintype "passive"))
      (node (ref "C40") (pin "2") (pinfunction "2_2") (pintype "passive"))
      (node (ref "C41") (pin "1") (pinfunction "1_1") (pintype "passive"))
      (node (ref "C42") (pin "1") (pinfunction "1_1") (pintype "passive"))
      (node (ref "C43") (pin "1") (pinfunction "1_1") (pintype "passive"))
      (node (ref "C44") (pin "1") (pinfunction "1_1") (pintype "passive"))
      (node (ref "C46") (pin "-") (pinfunction "-_-") (pintype "passive"))
      (node (ref "C47") (pin "-") (pinfunction "-_-") (pintype "passive"))
      (node (ref "C48") (pin "-") (pinfunction "-_-") (pintype "passive"))
      (node (ref "C49") (pin "+") (pinfunction "+_+") (pintype "passive"))
      (node (ref "C5") (pin "-") (pinfunction "-_-") (pintype "passive"))
      (node (ref "C50") (pin "+") (pinfunction "+_+") (pintype "passive"))
      (node (ref "C51") (pin "+") (pinfunction "+_+") (pintype "passive"))
      (node (ref "C57") (pin "1") (pinfunction "1_1") (pintype "passive"))
      (node (ref "C58") (pin "2") (pinfunction "2_2") (pintype "passive"))
      (node (ref "C59") (pin "1") (pinfunction "1_1") (pintype "passive"))
      (node (ref "C6") (pin "-") (pinfunction "-_-") (pintype "passive"))
      (node (ref "C60") (pin "2") (pinfunction "2_2") (pintype "passive"))
      (node (ref "C61") (pin "2") (pinfunction "2_2") (pintype "passive"))
      (node (ref "C62") (pin "2") (pinfunction "2_2") (pintype "passive"))
      (node (ref "C63") (pin "2") (pinfunction "2_2") (pintype "passive"))
      (node (ref "C64") (pin "2") (pinfunction "2_2") (pintype "passive"))
      (node (ref "C65") (pin "2") (pinfunction "2_2") (pintype "passive"))
      (node (ref "C66") (pin "2") (pinfunction "2_2") (pintype "passive"))
      (node (ref "C7") (pin "-") (pinfunction "-_-") (pintype "passive"))
      (node (ref "C8") (pin "-") (pinfunction "-_-") (pintype "passive"))
      (node (ref "C9") (pin "2") (pinfunction "2_2") (pintype "passive"))
      (node (ref "CON_BACKPLANE") (pin "10") (pinfunction "10_10") (pintype "bidirectional"))
      (node (ref "CON_BACKPLANE") (pin "15") (pinfunction "15_15") (pintype "bidirectional"))
      (node (ref "CON_BACKPLANE") (pin "25") (pinfunction "25_25") (pintype "bidirectional"))
      (node (ref "CON_BACKPLANE") (pin "26") (pinfunction "26_26") (pintype "bidirectional"))
      (node (ref "CON_BACKPLANE") (pin "27") (pinfunction "27_27") (pintype "bidirectional"))
      (node (ref "CON_BACKPLANE") (pin "28") (pinfunction "28_28") (pintype "bidirectional"))
      (node (ref "CON_BACKPLANE") (pin "29") (pinfunction "29_29") (pintype "bidirectional"))
      (node (ref "CON_BACKPLANE") (pin "3") (pinfunction "3_3") (pintype "bidirectional"))
      (node (ref "CON_BACKPLANE") (pin "30") (pinfunction "30_30") (pintype "bidirectional"))
      (node (ref "CON_BACKPLANE") (pin "31") (pinfunction "31_31") (pintype "bidirectional"))
      (node (ref "CON_BACKPLANE") (pin "32") (pinfunction "32_32") (pintype "bidirectional"))
      (node (ref "CON_BACKPLANE") (pin "4") (pinfunction "4_4") (pintype "bidirectional"))
      (node (ref "CON_BACKPLANE") (pin "7") (pinfunction "7_7") (pintype "bidirectional"))
      (node (ref "CON_BACKPLANE") (pin "8") (pinfunction "8_8") (pintype "bidirectional"))
      (node (ref "CON_EXT_CH1") (pin "G1") (pinfunction "G_G1") (pintype "passive"))
      (node (ref "CON_EXT_CH1") (pin "G2") (pinfunction "G_G2") (pintype "passive"))
      (node (ref "CON_EXT_CH1") (pin "G3") (pinfunction "G_G3") (pintype "passive"))
      (node (ref "CON_EXT_CH1") (pin "G4") (pinfunction "G_G4") (pintype "passive"))
      (node (ref "CON_EXT_CH2") (pin "G1") (pinfunction "G_G1") (pintype "passive"))
      (node (ref "CON_EXT_CH2") (pin "G2") (pinfunction "G_G2") (pintype "passive"))
      (node (ref "CON_EXT_CH2") (pin "G3") (pinfunction "G_G3") (pintype "passive"))
      (node (ref "CON_EXT_CH2") (pin "G4") (pinfunction "G_G4") (pintype "passive"))
      (node (ref "CON_INT_CH1") (pin "G1") (pinfunction "GND_G1") (pintype "passive"))
      (node (ref "CON_INT_CH1") (pin "G2") (pinfunction "GND_G2") (pintype "passive"))
      (node (ref "CON_INT_CH2") (pin "G1") (pinfunction "GND_G1") (pintype "passive"))
      (node (ref "CON_INT_CH2") (pin "G2") (pinfunction "GND_G2") (pintype "passive"))
      (node (ref "IC1") (pin "1") (pinfunction "GND_1") (pintype "input"))
      (node (ref "IC11") (pin "1") (pinfunction "A0_1") (pintype "bidirectional"))
      (node (ref "IC11") (pin "2") (pinfunction "A1_2") (pintype "bidirectional"))
      (node (ref "IC11") (pin "3") (pinfunction "A2_3") (pintype "bidirectional"))
      (node (ref "IC11") (pin "8") (pinfunction "GND_8") (pintype "power_in"))
      (node (ref "IC2") (pin "1") (pinfunction "GND_1") (pintype "input"))
      (node (ref "IC3") (pin "4") (pinfunction "GND_4") (pintype "bidirectional"))
      (node (ref "IC4") (pin "2") (pinfunction "V-_2") (pintype "bidirectional"))
      (node (ref "IC5") (pin "13") (pinfunction "-VCLAMP_13") (pintype "power_in"))
      (node (ref "IC5") (pin "14") (pinfunction "-VS_14") (pintype "power_in"))
      (node (ref "IC5") (pin "15") (pinfunction "-VS_15") (pintype "power_in"))
      (node (ref "IC5") (pin "16") (pinfunction "DGND_16") (pintype "power_in"))
      (node (ref "IC5") (pin "17") (pinfunction "EP_17") (pintype "power_in"))
      (node (ref "IC6") (pin "13") (pinfunction "-VCLAMP_13") (pintype "power_in"))
      (node (ref "IC6") (pin "14") (pinfunction "-VS_14") (pintype "power_in"))
      (node (ref "IC6") (pin "15") (pinfunction "-VS_15") (pintype "power_in"))
      (node (ref "IC6") (pin "16") (pinfunction "DGND_16") (pintype "power_in"))
      (node (ref "IC6") (pin "17") (pinfunction "EP_17") (pintype "power_in"))
      (node (ref "IC7") (pin "1") (pinfunction "GND_1") (pintype "input"))
      (node (ref "IC8") (pin "1") (pinfunction "GND_1") (pintype "bidirectional"))
      (node (ref "LED_-5V_FRONTEND") (pin "A") (pinfunction "A_A") (pintype "passive"))
      (node (ref "LED_SHORT_CH1") (pin "-") (pinfunction "C_-") (pintype "passive"))
      (node (ref "LED_SHORT_CH2") (pin "-") (pinfunction "C_-") (pintype "passive"))
      (node (ref "OSC1") (pin "2") (pinfunction "GND_2") (pintype "bidirectional"))
      (node (ref "R1") (pin "2") (pinfunction "2_2") (pintype "passive"))
      (node (ref "R18") (pin "2") (pinfunction "2_2") (pintype "passive"))
      (node (ref "R2") (pin "2") (pinfunction "2_2") (pintype "passive"))
      (node (ref "R22") (pin "2") (pinfunction "2_2") (pintype "passive"))
      (node (ref "R23") (pin "2") (pinfunction "2_2") (pintype "passive"))
      (node (ref "R4") (pin "1") (pinfunction "1_1") (pintype "passive"))
      (node (ref "R5") (pin "1") (pinfunction "1_1") (pintype "passive"))
      (node (ref "RD") (pin "12") (pinfunction "PGND_12") (pintype "power_in"))
      (node (ref "RD") (pin "18") (pinfunction "PGND_18") (pintype "power_in"))
      (node (ref "RD") (pin "21") (pinfunction "GND_21") (pintype "power_in"))
      (node (ref "RD") (pin "9") (pinfunction "GND_9") (pintype "power_in"))
      (node (ref "RELAY1") (pin "4") (pinfunction "4_4") (pintype "passive"))
      (node (ref "RELAY2") (pin "4") (pinfunction "4_4") (pintype "passive"))
      (node (ref "TP_GND1") (pin "P$1") (pinfunction "P$1_P$1") (pintype "bidirectional"))
      (node (ref "TP_GND2") (pin "P$1") (pinfunction "P$1_P$1") (pintype "bidirectional"))
      (node (ref "TP_GND3") (pin "P$1") (pinfunction "P$1_P$1") (pintype "bidirectional"))
      (node (ref "TP_GND4") (pin "P$1") (pinfunction "P$1_P$1") (pintype "bidirectional"))
    )
    (net (code "22") (name "I2C_NINT") (class "Default")
      (node (ref "CON_BACKPLANE") (pin "22") (pinfunction "22_22") (pintype "bidirectional"))
      (node (ref "IC11") (pin "13") (pinfunction "~{INT}_13") (pintype "bidirectional"))
      (node (ref "TP_I2C_NINT") (pin "P$1") (pinfunction "P$1_P$1") (pintype "bidirectional"))
    )
    (net (code "23") (name "I2C_SCL") (class "Default")
      (node (ref "CON_BACKPLANE") (pin "24") (pinfunction "24_24") (pintype "bidirectional"))
      (node (ref "IC11") (pin "14") (pinfunction "SCL_14") (pintype "bidirectional"))
      (node (ref "TP_I2C_SCL") (pin "P$1") (pinfunction "P$1_P$1") (pintype "bidirectional"))
    )
    (net (code "24") (name "I2C_SDA") (class "Default")
      (node (ref "CON_BACKPLANE") (pin "23") (pinfunction "23_23") (pintype "bidirectional"))
      (node (ref "IC11") (pin "15") (pinfunction "SDA_15") (pintype "bidirectional"))
      (node (ref "TP_I2C_SDA") (pin "P$1") (pinfunction "P$1_P$1") (pintype "bidirectional"))
    )
    (net (code "25") (name "Net-(ADC-DIN)") (class "Default")
      (node (ref "ADC") (pin "21") (pinfunction "DIN_21") (pintype "power_in"))
      (node (ref "R5") (pin "2") (pinfunction "2_2") (pintype "passive"))
    )
    (net (code "26") (name "Net-(ADC-DNC{slash}DGND)") (class "Default")
      (node (ref "ADC") (pin "20") (pinfunction "DNC/DGND_20") (pintype "power_in"))
      (node (ref "R4") (pin "2") (pinfunction "2_2") (pintype "passive"))
    )
    (net (code "27") (name "Net-(ADC-DREGCAP)") (class "Default")
      (node (ref "ADC") (pin "34") (pinfunction "DREGCAP_34") (pintype "output"))
      (node (ref "C20") (pin "1") (pinfunction "1_1") (pintype "passive"))
      (node (ref "C21") (pin "1") (pinfunction "1_1") (pintype "passive"))
    )
    (net (code "28") (name "Net-(ADC-REGCAPA)") (class "Default")
      (node (ref "ADC") (pin "61") (pinfunction "REGCAPA_61") (pintype "output"))
      (node (ref "C24") (pin "1") (pinfunction "1_1") (pintype "passive"))
      (node (ref "C25") (pin "1") (pinfunction "1_1") (pintype "passive"))
    )
    (net (code "29") (name "Net-(ADC-REGCAPB)") (class "Default")
      (node (ref "ADC") (pin "52") (pinfunction "REGCAPB_52") (pintype "output"))
      (node (ref "C22") (pin "1") (pinfunction "1_1") (pintype "passive"))
      (node (ref "C23") (pin "1") (pinfunction "1_1") (pintype "passive"))
    )
    (net (code "30") (name "Net-(ADC-VCM)") (class "Default")
      (node (ref "ADC") (pin "59") (pinfunction "VCM_59") (pintype "output"))
      (node (ref "R14") (pin "1") (pinfunction "1_1") (pintype "passive"))
    )
    (net (code "31") (name "Net-(ADC-~{START})") (class "Default")
      (node (ref "ADC") (pin "37") (pinfunction "~{START}_37") (pintype "input"))
      (node (ref "R3") (pin "2") (pinfunction "2_2") (pintype "passive"))
    )
    (net (code "32") (name "Net-(ADC-~{SYNC_IN})") (class "Default")
      (node (ref "ADC") (pin "36") (pinfunction "~{SYNC_IN}_36") (pintype "input"))
      (node (ref "ADC") (pin "38") (pinfunction "~{SYNC_OUT}_38") (pintype "output"))
    )
    (net (code "33") (name "Net-(C35-Pad1)") (class "Default")
      (node (ref "C35") (pin "1") (pinfunction "1_1") (pintype "passive"))
      (node (ref "R7") (pin "1") (pinfunction "1_1") (pintype "passive"))
    )
    (net (code "34") (name "Net-(CON_INT_CH1-SIG)") (class "Default")
      (node (ref "CON_EXT_CH1") (pin "S") (pinfunction "S_S") (pintype "passive"))
      (node (ref "CON_INT_CH1") (pin "S") (pinfunction "SIG_S") (pintype "passive"))
      (node (ref "RELAY1") (pin "2") (pinfunction "2_2") (pintype "passive"))
    )
    (net (code "35") (name "Net-(CON_INT_CH2-SIG)") (class "Default")
      (node (ref "CON_EXT_CH2") (pin "S") (pinfunction "S_S") (pintype "passive"))
      (node (ref "CON_INT_CH2") (pin "S") (pinfunction "SIG_S") (pintype "passive"))
      (node (ref "RELAY2") (pin "2") (pinfunction "2_2") (pintype "passive"))
    )
    (net (code "36") (name "Net-(IC2-IN)") (class "Default")
      (node (ref "C7") (pin "+") (pinfunction "+_+") (pintype "passive"))
      (node (ref "IC2") (pin "3") (pinfunction "IN_3") (pintype "input"))
      (node (ref "L1") (pin "2") (pinfunction "2_2") (pintype "passive"))
    )
    (net (code "37") (name "Net-(IC4-+)") (class "Default")
      (node (ref "C32") (pin "2") (pinfunction "2_2") (pintype "passive"))
      (node (ref "IC4") (pin "3") (pinfunction "+_3") (pintype "bidirectional"))
      (node (ref "R6") (pin "2") (pinfunction "2_2") (pintype "passive"))
    )
    (net (code "38") (name "Net-(IC4--)") (class "Default")
      (node (ref "C35") (pin "2") (pinfunction "2_2") (pintype "passive"))
      (node (ref "IC4") (pin "4") (pinfunction "-_4") (pintype "bidirectional"))
      (node (ref "R8") (pin "1") (pinfunction "1_1") (pintype "passive"))
    )
    (net (code "39") (name "Net-(IC4-VOUT)") (class "Default")
      (node (ref "IC4") (pin "1") (pinfunction "VOUT_1") (pintype "bidirectional"))
      (node (ref "R7") (pin "2") (pinfunction "2_2") (pintype "passive"))
      (node (ref "R9") (pin "1") (pinfunction "1_1") (pintype "passive"))
    )
    (net (code "40") (name "Net-(IC5-+FB)") (class "Default")
      (node (ref "C54") (pin "1") (pinfunction "1_1") (pintype "passive"))
      (node (ref "IC5") (pin "4") (pinfunction "+FB_4") (pintype "input"))
      (node (ref "R16") (pin "1") (pinfunction "1_1") (pintype "passive"))
    )
    (net (code "41") (name "Net-(IC5-+IN)") (class "Default")
      (node (ref "C53") (pin "1") (pinfunction "1_1") (pintype "passive"))
      (node (ref "IC5") (pin "2") (pinfunction "+IN_2") (pintype "input"))
      (node (ref "R15") (pin "2") (pinfunction "2_2") (pintype "passive"))
      (node (ref "R17") (pin "1") (pinfunction "1_1") (pintype "passive"))
    )
    (net (code "42") (name "Net-(IC5-+OUT)") (class "Default")
      (node (ref "IC5") (pin "10") (pinfunction "+OUT_10") (pintype "output"))
      (node (ref "R10") (pin "2") (pinfunction "2_2") (pintype "passive"))
    )
    (net (code "43") (name "Net-(IC5--FB)") (class "Default")
      (node (ref "C53") (pin "2") (pinfunction "2_2") (pintype "passive"))
      (node (ref "IC5") (pin "1") (pinfunction "-FB_1") (pintype "input"))
      (node (ref "R15") (pin "1") (pinfunction "1_1") (pintype "passive"))
    )
    (net (code "44") (name "Net-(IC5--IN)") (class "Default")
      (node (ref "C54") (pin "2") (pinfunction "2_2") (pintype "passive"))
      (node (ref "IC5") (pin "3") (pinfunction "-IN_3") (pintype "input"))
      (node (ref "R16") (pin "2") (pinfunction "2_2") (pintype "passive"))
      (node (ref "R18") (pin "1") (pinfunction "1_1") (pintype "passive"))
    )
    (net (code "45") (name "Net-(IC5--OUT)") (class "Default")
      (node (ref "IC5") (pin "11") (pinfunction "-OUT_11") (pintype "output"))
      (node (ref "R11") (pin "2") (pinfunction "2_2") (pintype "passive"))
    )
    (net (code "46") (name "Net-(IC6-+FB)") (class "Default")
      (node (ref "C56") (pin "1") (pinfunction "1_1") (pintype "passive"))
      (node (ref "IC6") (pin "4") (pinfunction "+FB_4") (pintype "input"))
      (node (ref "R20") (pin "1") (pinfunction "1_1") (pintype "passive"))
    )
    (net (code "47") (name "Net-(IC6-+IN)") (class "Default")
      (node (ref "C55") (pin "1") (pinfunction "1_1") (pintype "passive"))
      (node (ref "IC6") (pin "2") (pinfunction "+IN_2") (pintype "input"))
      (node (ref "R19") (pin "2") (pinfunction "2_2") (pintype "passive"))
      (node (ref "R21") (pin "1") (pinfunction "1_1") (pintype "passive"))
    )
    (net (code "48") (name "Net-(IC6-+OUT)") (class "Default")
      (node (ref "IC6") (pin "10") (pinfunction "+OUT_10") (pintype "output"))
      (node (ref "R12") (pin "2") (pinfunction "2_2") (pintype "passive"))
    )
    (net (code "49") (name "Net-(IC6--FB)") (class "Default")
      (node (ref "C55") (pin "2") (pinfunction "2_2") (pintype "passive"))
      (node (ref "IC6") (pin "1") (pinfunction "-FB_1") (pintype "input"))
      (node (ref "R19") (pin "1") (pinfunction "1_1") (pintype "passive"))
    )
    (net (code "50") (name "Net-(IC6--IN)") (class "Default")
      (node (ref "C56") (pin "2") (pinfunction "2_2") (pintype "passive"))
      (node (ref "IC6") (pin "3") (pinfunction "-IN_3") (pintype "input"))
      (node (ref "R20") (pin "2") (pinfunction "2_2") (pintype "passive"))
      (node (ref "R22") (pin "1") (pinfunction "1_1") (pintype "passive"))
    )
    (net (code "51") (name "Net-(IC6--OUT)") (class "Default")
      (node (ref "IC6") (pin "11") (pinfunction "-OUT_11") (pintype "output"))
      (node (ref "R13") (pin "2") (pinfunction "2_2") (pintype "passive"))
    )
    (net (code "52") (name "Net-(IC7-IN)") (class "Default")
      (node (ref "C47") (pin "+") (pinfunction "+_+") (pintype "passive"))
      (node (ref "IC7") (pin "3") (pinfunction "IN_3") (pintype "input"))
      (node (ref "L2") (pin "2") (pinfunction "2_2") (pintype "passive"))
    )
    (net (code "53") (name "Net-(IC8-VIN)") (class "Default")
      (node (ref "C50") (pin "-") (pinfunction "-_-") (pintype "passive"))
      (node (ref "IC8") (pin "2") (pinfunction "VIN_2") (pintype "bidirectional"))
      (node (ref "L3") (pin "1") (pinfunction "1_1") (pintype "passive"))
    )
    (net (code "54") (name "Net-(IC9-+IN)") (class "Default")
      (node (ref "C61") (pin "1") (pinfunction "1_1") (pintype "passive"))
      (node (ref "IC9") (pin "3") (pinfunction "+IN_3") (pintype "input"))
      (node (ref "R25") (pin "1") (pinfunction "1_1") (pintype "passive"))
    )
    (net (code "55") (name "Net-(IC9--IN)") (class "Default")
      (node (ref "IC9") (pin "2") (pinfunction "-IN_2") (pintype "input"))
      (node (ref "IC9") (pin "6") (pinfunction "OUT_6") (pintype "output"))
      (node (ref "R17") (pin "2") (pinfunction "2_2") (pintype "passive"))
    )
    (net (code "56") (name "Net-(IC9-ON1)") (class "Default")
      (node (ref "IC9") (pin "1") (pinfunction "ON1_1") (pintype "passive"))
      (node (ref "POT1") (pin "3") (pinfunction "3_3") (pintype "passive"))
    )
    (net (code "57") (name "Net-(IC9-OPT)") (class "Default")
      (node (ref "IC9") (pin "5") (pinfunction "OPT_5") (pintype "passive"))
      (node (ref "POT1") (pin "1") (pinfunction "1_1") (pintype "passive"))
    )
    (net (code "58") (name "Net-(IC10-+IN)") (class "Default")
      (node (ref "C62") (pin "1") (pinfunction "1_1") (pintype "passive"))
      (node (ref "IC10") (pin "3") (pinfunction "+IN_3") (pintype "input"))
      (node (ref "R26") (pin "1") (pinfunction "1_1") (pintype "passive"))
    )
    (net (code "59") (name "Net-(IC10--IN)") (class "Default")
      (node (ref "IC10") (pin "2") (pinfunction "-IN_2") (pintype "input"))
      (node (ref "IC10") (pin "6") (pinfunction "OUT_6") (pintype "output"))
      (node (ref "R21") (pin "2") (pinfunction "2_2") (pintype "passive"))
    )
    (net (code "60") (name "Net-(IC10-ON1)") (class "Default")
      (node (ref "IC10") (pin "1") (pinfunction "ON1_1") (pintype "passive"))
      (node (ref "POT2") (pin "3") (pinfunction "3_3") (pintype "passive"))
    )
    (net (code "61") (name "Net-(IC10-OPT)") (class "Default")
      (node (ref "IC10") (pin "5") (pinfunction "OPT_5") (pintype "passive"))
      (node (ref "POT2") (pin "1") (pinfunction "1_1") (pintype "passive"))
    )
    (net (code "62") (name "Net-(LED_+3.3V-PadC)") (class "Default")
      (node (ref "LED_+3.3V") (pin "C") (pinfunction "C_C") (pintype "passive"))
      (node (ref "R1") (pin "1") (pinfunction "1_1") (pintype "passive"))
    )
    (net (code "63") (name "Net-(LED_+5V_ADC-PadC)") (class "Default")
      (node (ref "LED_+5V_ADC") (pin "C") (pinfunction "C_C") (pintype "passive"))
      (node (ref "R2") (pin "1") (pinfunction "1_1") (pintype "passive"))
    )
    (net (code "64") (name "Net-(LED_+5V_FRONTEND-PadC)") (class "Default")
      (node (ref "LED_+5V_FRONTEND") (pin "C") (pinfunction "C_C") (pintype "passive"))
      (node (ref "R23") (pin "1") (pinfunction "1_1") (pintype "passive"))
    )
    (net (code "65") (name "Net-(LED_-5V_FRONTEND-PadC)") (class "Default")
      (node (ref "LED_-5V_FRONTEND") (pin "C") (pinfunction "C_C") (pintype "passive"))
      (node (ref "R24") (pin "1") (pinfunction "1_1") (pintype "passive"))
    )
    (net (code "66") (name "Net-(LED_SHORT_CH1-A)") (class "Default")
      (node (ref "LED_SHORT_CH1") (pin "+") (pinfunction "A_+") (pintype "passive"))
      (node (ref "R31") (pin "2") (pinfunction "2_2") (pintype "passive"))
    )
    (net (code "67") (name "Net-(LED_SHORT_CH2-A)") (class "Default")
      (node (ref "LED_SHORT_CH2") (pin "+") (pinfunction "A_+") (pintype "passive"))
      (node (ref "R32") (pin "2") (pinfunction "2_2") (pintype "passive"))
    )
    (net (code "68") (name "Net-(R6-Pad1)") (class "Default")
      (node (ref "R6") (pin "1") (pinfunction "1_1") (pintype "passive"))
      (node (ref "SJ1") (pin "3") (pinfunction "3_3") (pintype "passive"))
    )
    (net (code "69") (name "Net-(R25-Pad2)") (class "Default")
      (node (ref "R25") (pin "2") (pinfunction "2_2") (pintype "passive"))
      (node (ref "RELAY1") (pin "3") (pinfunction "3_3") (pintype "passive"))
    )
    (net (code "70") (name "Net-(R26-Pad2)") (class "Default")
      (node (ref "R26") (pin "2") (pinfunction "2_2") (pintype "passive"))
      (node (ref "RELAY2") (pin "3") (pinfunction "3_3") (pintype "passive"))
    )
    (net (code "71") (name "Net-(R31-Pad1)") (class "Default")
      (node (ref "R31") (pin "1") (pinfunction "1_1") (pintype "passive"))
      (node (ref "RELAY1") (pin "5") (pinfunction "5_5") (pintype "passive"))
    )
    (net (code "72") (name "Net-(R32-Pad1)") (class "Default")
      (node (ref "R32") (pin "1") (pinfunction "1_1") (pintype "passive"))
      (node (ref "RELAY2") (pin "5") (pinfunction "5_5") (pintype "passive"))
    )
    (net (code "73") (name "Net-(SJ1-Pad1)") (class "Default")
      (node (ref "SJ1") (pin "1") (pinfunction "1_1") (pintype "passive"))
      (node (ref "SJ2") (pin "3") (pinfunction "3_3") (pintype "passive"))
    )
    (net (code "74") (name "RD_NCS") (class "Default")
      (node (ref "IC11") (pin "6") (pinfunction "P2_6") (pintype "bidirectional"))
      (node (ref "RD") (pin "4") (pinfunction "~{CS}_4") (pintype "input"))
      (node (ref "TP_RD_NCS") (pin "P$1") (pinfunction "P$1_P$1") (pintype "bidirectional"))
    )
    (net (code "75") (name "RD_NRESET") (class "Default")
      (node (ref "IC11") (pin "7") (pinfunction "P3_7") (pintype "bidirectional"))
      (node (ref "RD") (pin "3") (pinfunction "~{RESET}_3") (pintype "input"))
      (node (ref "TP_RD_NRESET") (pin "P$1") (pinfunction "P$1_P$1") (pintype "bidirectional"))
    )
    (net (code "76") (name "RD_OUT1") (class "Default")
      (node (ref "R27") (pin "1") (pinfunction "1_1") (pintype "passive"))
      (node (ref "RD") (pin "20") (pinfunction "OUT1_20") (pintype "output"))
      (node (ref "RELAY1") (pin "1") (pinfunction "1_1") (pintype "passive"))
    )
    (net (code "77") (name "RD_OUT2") (class "Default")
      (node (ref "R28") (pin "1") (pinfunction "1_1") (pintype "passive"))
      (node (ref "RD") (pin "19") (pinfunction "OUT2_19") (pintype "output"))
      (node (ref "RELAY1") (pin "8") (pinfunction "8_8") (pintype "passive"))
    )
    (net (code "78") (name "RD_OUT3") (class "Default")
      (node (ref "R29") (pin "1") (pinfunction "1_1") (pintype "passive"))
      (node (ref "RD") (pin "17") (pinfunction "OUT3_17") (pintype "output"))
      (node (ref "RELAY2") (pin "1") (pinfunction "1_1") (pintype "passive"))
    )
    (net (code "79") (name "RD_OUT4") (class "Default")
      (node (ref "R30") (pin "1") (pinfunction "1_1") (pintype "passive"))
      (node (ref "RD") (pin "16") (pinfunction "OUT4_16") (pintype "output"))
      (node (ref "RELAY2") (pin "8") (pinfunction "8_8") (pintype "passive"))
    )
    (net (code "80") (name "SPI_CONFIG_ADC_NCS") (class "Default")
      (node (ref "ADC") (pin "16") (pinfunction "ST0/~{CS}_16") (pintype "input"))
      (node (ref "IC11") (pin "5") (pinfunction "P1_5") (pintype "bidirectional"))
      (node (ref "TP_SPI_CONFIG_ADC_NCS") (pin "P$1") (pinfunction "P$1_P$1") (pintype "bidirectional"))
    )
    (net (code "81") (name "SPI_CONFIG_CLK") (class "Default")
      (node (ref "ADC") (pin "17") (pinfunction "SCLK_17") (pintype "input"))
      (node (ref "CON_BACKPLANE") (pin "21") (pinfunction "21_21") (pintype "bidirectional"))
      (node (ref "RD") (pin "6") (pinfunction "SCLK_6") (pintype "input"))
      (node (ref "TP_SPI_CONFIG_CLK") (pin "P$1") (pinfunction "P$1_P$1") (pintype "bidirectional"))
    )
    (net (code "82") (name "SPI_CONFIG_MISO") (class "Default")
      (node (ref "ADC") (pin "19") (pinfunction "DEC0/SDO_19") (pintype "output"))
      (node (ref "CON_BACKPLANE") (pin "19") (pinfunction "19_19") (pintype "bidirectional"))
      (node (ref "RD") (pin "7") (pinfunction "DOUT_7") (pintype "output"))
      (node (ref "TP_SPI_CONFIG_MISO") (pin "P$1") (pinfunction "P$1_P$1") (pintype "bidirectional"))
    )
    (net (code "83") (name "SPI_CONFIG_MOSI") (class "Default")
      (node (ref "ADC") (pin "18") (pinfunction "DEC1/SDI_18") (pintype "input"))
      (node (ref "CON_BACKPLANE") (pin "20") (pinfunction "20_20") (pintype "bidirectional"))
      (node (ref "RD") (pin "5") (pinfunction "DIN_5") (pintype "input"))
      (node (ref "TP_SPI_CONFIG_MOSI") (pin "P$1") (pinfunction "P$1_P$1") (pintype "bidirectional"))
    )
    (net (code "84") (name "SPI_DATA_CLK") (class "Default")
      (node (ref "ADC") (pin "28") (pinfunction "DCLK_28") (pintype "output"))
      (node (ref "CON_BACKPLANE") (pin "17") (pinfunction "17_17") (pintype "bidirectional"))
      (node (ref "TP_SPI_DATA_CLK") (pin "P$1") (pinfunction "P$1_P$1") (pintype "bidirectional"))
    )
    (net (code "85") (name "SPI_DATA_MOSI") (class "Default")
      (node (ref "ADC") (pin "27") (pinfunction "DOUT0_27") (pintype "output"))
      (node (ref "CON_BACKPLANE") (pin "18") (pinfunction "18_18") (pintype "bidirectional"))
      (node (ref "TP_SPI_DATA_MOSI") (pin "P$1") (pinfunction "P$1_P$1") (pintype "bidirectional"))
    )
    (net (code "86") (name "SPI_DATA_NCS") (class "Default")
      (node (ref "ADC") (pin "29") (pinfunction "~{DRDY}_29") (pintype "output"))
      (node (ref "CON_BACKPLANE") (pin "16") (pinfunction "16_16") (pintype "bidirectional"))
      (node (ref "TP_SPI_DATA_NCS") (pin "P$1") (pinfunction "P$1_P$1") (pintype "bidirectional"))
    )
    (net (code "87") (name "VCM") (class "Default")
      (node (ref "C40") (pin "1") (pinfunction "1_1") (pintype "passive"))
      (node (ref "IC5") (pin "9") (pinfunction "VOCM_9") (pintype "passive"))
      (node (ref "IC6") (pin "9") (pinfunction "VOCM_9") (pintype "passive"))
      (node (ref "R14") (pin "2") (pinfunction "2_2") (pintype "passive"))
    )
    (net (code "88") (name "VREF") (class "Default")
      (node (ref "C31") (pin "2") (pinfunction "2_2") (pintype "passive"))
      (node (ref "IC3") (pin "6") (pinfunction "VOUT_6") (pintype "bidirectional"))
      (node (ref "SJ1") (pin "2") (pinfunction "2_2") (pintype "passive"))
    )
    (net (code "89") (name "VREF_BUF") (class "Default")
      (node (ref "R8") (pin "2") (pinfunction "2_2") (pintype "passive"))
      (node (ref "R9") (pin "2") (pinfunction "2_2") (pintype "passive"))
      (node (ref "SJ2") (pin "1") (pinfunction "1_1") (pintype "passive"))
    )
    (net (code "90") (name "unconnected-(ADC-DNC22-Pad22)") (class "Default")
      (node (ref "ADC") (pin "22") (pinfunction "DNC22_22") (pintype "no_connect"))
    )
    (net (code "91") (name "unconnected-(ADC-DNC23-Pad23)") (class "Default")
      (node (ref "ADC") (pin "23") (pinfunction "DNC23_23") (pintype "no_connect"))
    )
    (net (code "92") (name "unconnected-(ADC-DOUT1-Pad26)") (class "Default")
      (node (ref "ADC") (pin "26") (pinfunction "DOUT1_26") (pintype "output"))
    )
    (net (code "93") (name "unconnected-(ADC-DOUT2-Pad25)") (class "Default")
      (node (ref "ADC") (pin "25") (pinfunction "DOUT2_25") (pintype "output"))
    )
    (net (code "94") (name "unconnected-(ADC-DOUT3-Pad24)") (class "Default")
      (node (ref "ADC") (pin "24") (pinfunction "DOUT3_24") (pintype "output"))
    )
    (net (code "95") (name "unconnected-(ADC-FILTER{slash}GPIO4-Pad11)") (class "Default")
      (node (ref "ADC") (pin "11") (pinfunction "FILTER/GPIO4_11") (pintype "bidirectional"))
    )
    (net (code "96") (name "unconnected-(ADC-MODE0{slash}GPIO0-Pad12)") (class "Default")
      (node (ref "ADC") (pin "12") (pinfunction "MODE0/GPIO0_12") (pintype "bidirectional"))
    )
    (net (code "97") (name "unconnected-(ADC-MODE1{slash}GPIO1-Pad13)") (class "Default")
      (node (ref "ADC") (pin "13") (pinfunction "MODE1/GPIO1_13") (pintype "bidirectional"))
    )
    (net (code "98") (name "unconnected-(ADC-MODE2{slash}GPIO2-Pad14)") (class "Default")
      (node (ref "ADC") (pin "14") (pinfunction "MODE2/GPIO2_14") (pintype "bidirectional"))
    )
    (net (code "99") (name "unconnected-(ADC-MODE3{slash}GPIO3-Pad15)") (class "Default")
      (node (ref "ADC") (pin "15") (pinfunction "MODE3/GPIO3_15") (pintype "bidirectional"))
    )
    (net (code "100") (name "unconnected-(IC3-TRIM-Pad5)") (class "Default")
      (node (ref "IC3") (pin "5") (pinfunction "TRIM_5") (pintype "bidirectional"))
    )
    (net (code "101") (name "unconnected-(IC4-~{PD}-Pad5)") (class "Default")
      (node (ref "IC4") (pin "5") (pinfunction "~{PD}_5") (pintype "bidirectional"))
    )
    (net (code "102") (name "unconnected-(IC9-ON2-Pad8)") (class "Default")
      (node (ref "IC9") (pin "8") (pinfunction "ON2_8") (pintype "passive"))
    )
    (net (code "103") (name "unconnected-(IC10-ON2-Pad8)") (class "Default")
      (node (ref "IC10") (pin "8") (pinfunction "ON2_8") (pintype "passive"))
    )
    (net (code "104") (name "unconnected-(IC11-P4-Pad9)") (class "Default")
      (node (ref "IC11") (pin "9") (pinfunction "P4_9") (pintype "bidirectional"))
    )
    (net (code "105") (name "unconnected-(IC11-P5-Pad10)") (class "Default")
      (node (ref "IC11") (pin "10") (pinfunction "P5_10") (pintype "bidirectional"))
    )
    (net (code "106") (name "unconnected-(IC11-P6-Pad11)") (class "Default")
      (node (ref "IC11") (pin "11") (pinfunction "P6_11") (pintype "bidirectional"))
    )
    (net (code "107") (name "unconnected-(IC11-P7-Pad12)") (class "Default")
      (node (ref "IC11") (pin "12") (pinfunction "P7_12") (pintype "bidirectional"))
    )
    (net (code "108") (name "unconnected-(RD-OUT5-Pad14)") (class "Default")
      (node (ref "RD") (pin "14") (pinfunction "OUT5_14") (pintype "output"))
    )
    (net (code "109") (name "unconnected-(RD-OUT6-Pad13)") (class "Default")
      (node (ref "RD") (pin "13") (pinfunction "OUT6_13") (pintype "output"))
    )
    (net (code "110") (name "unconnected-(RD-OUT7-Pad11)") (class "Default")
      (node (ref "RD") (pin "11") (pinfunction "OUT7_11") (pintype "output"))
    )
    (net (code "111") (name "unconnected-(RD-OUT8-Pad10)") (class "Default")
      (node (ref "RD") (pin "10") (pinfunction "OUT8_10") (pintype "output"))
    )
    (net (code "112") (name "unconnected-(RELAY1-Pad7)") (class "Default")
      (node (ref "RELAY1") (pin "7") (pinfunction "7_7") (pintype "passive"))
    )
    (net (code "113") (name "unconnected-(RELAY2-Pad7)") (class "Default")
      (node (ref "RELAY2") (pin "7") (pinfunction "7_7") (pintype "passive"))
    )
  )
)
